# streams_v05.net
KiCad netlist of a schematic drawn in EAGLE
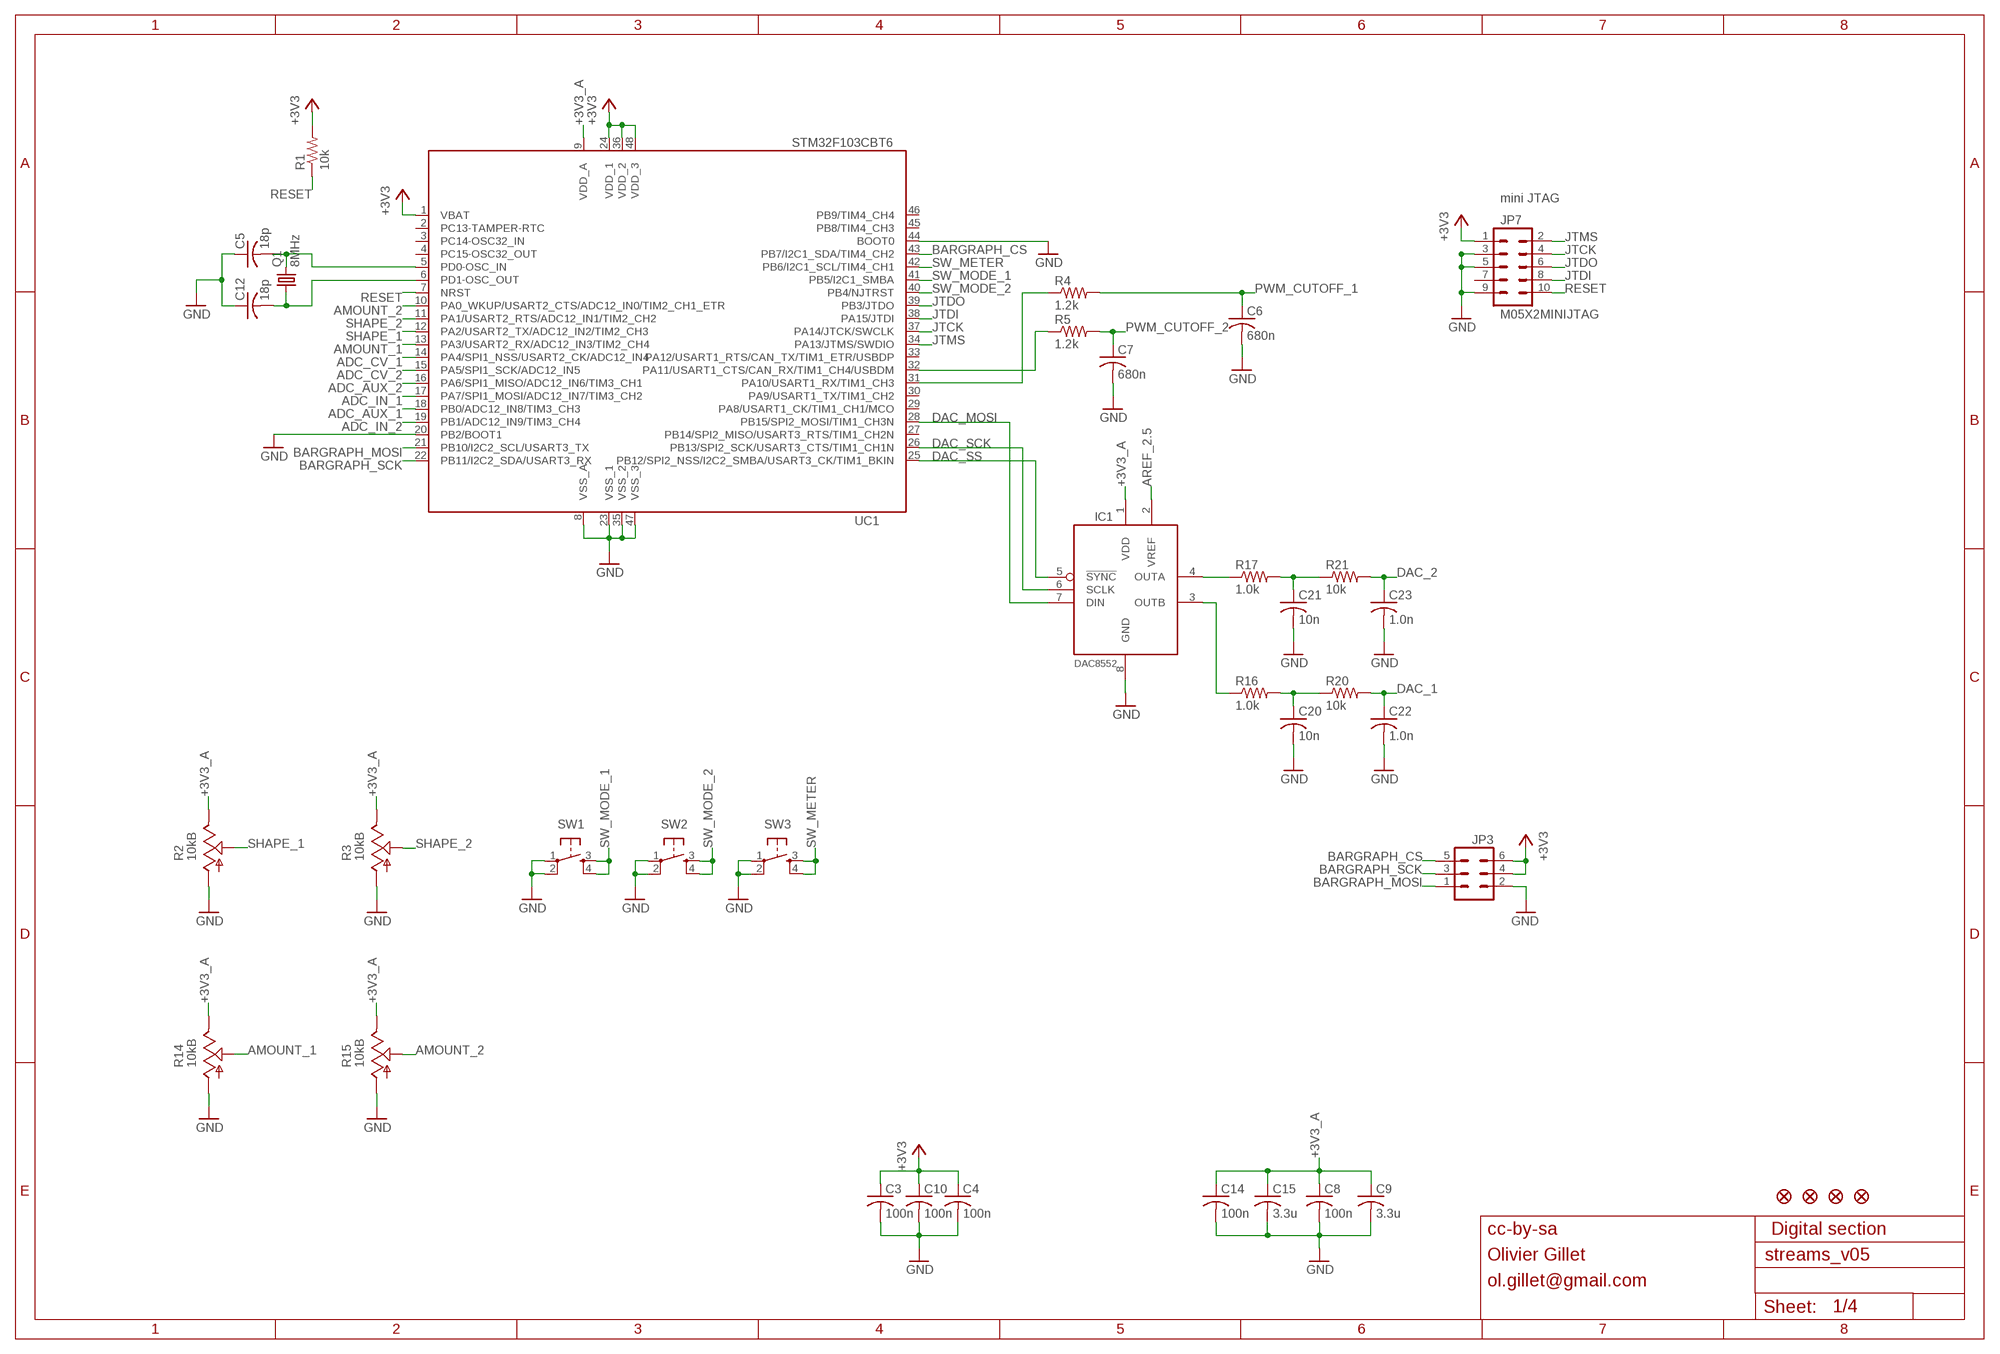
[diagram p0: schematic, sheet 1]
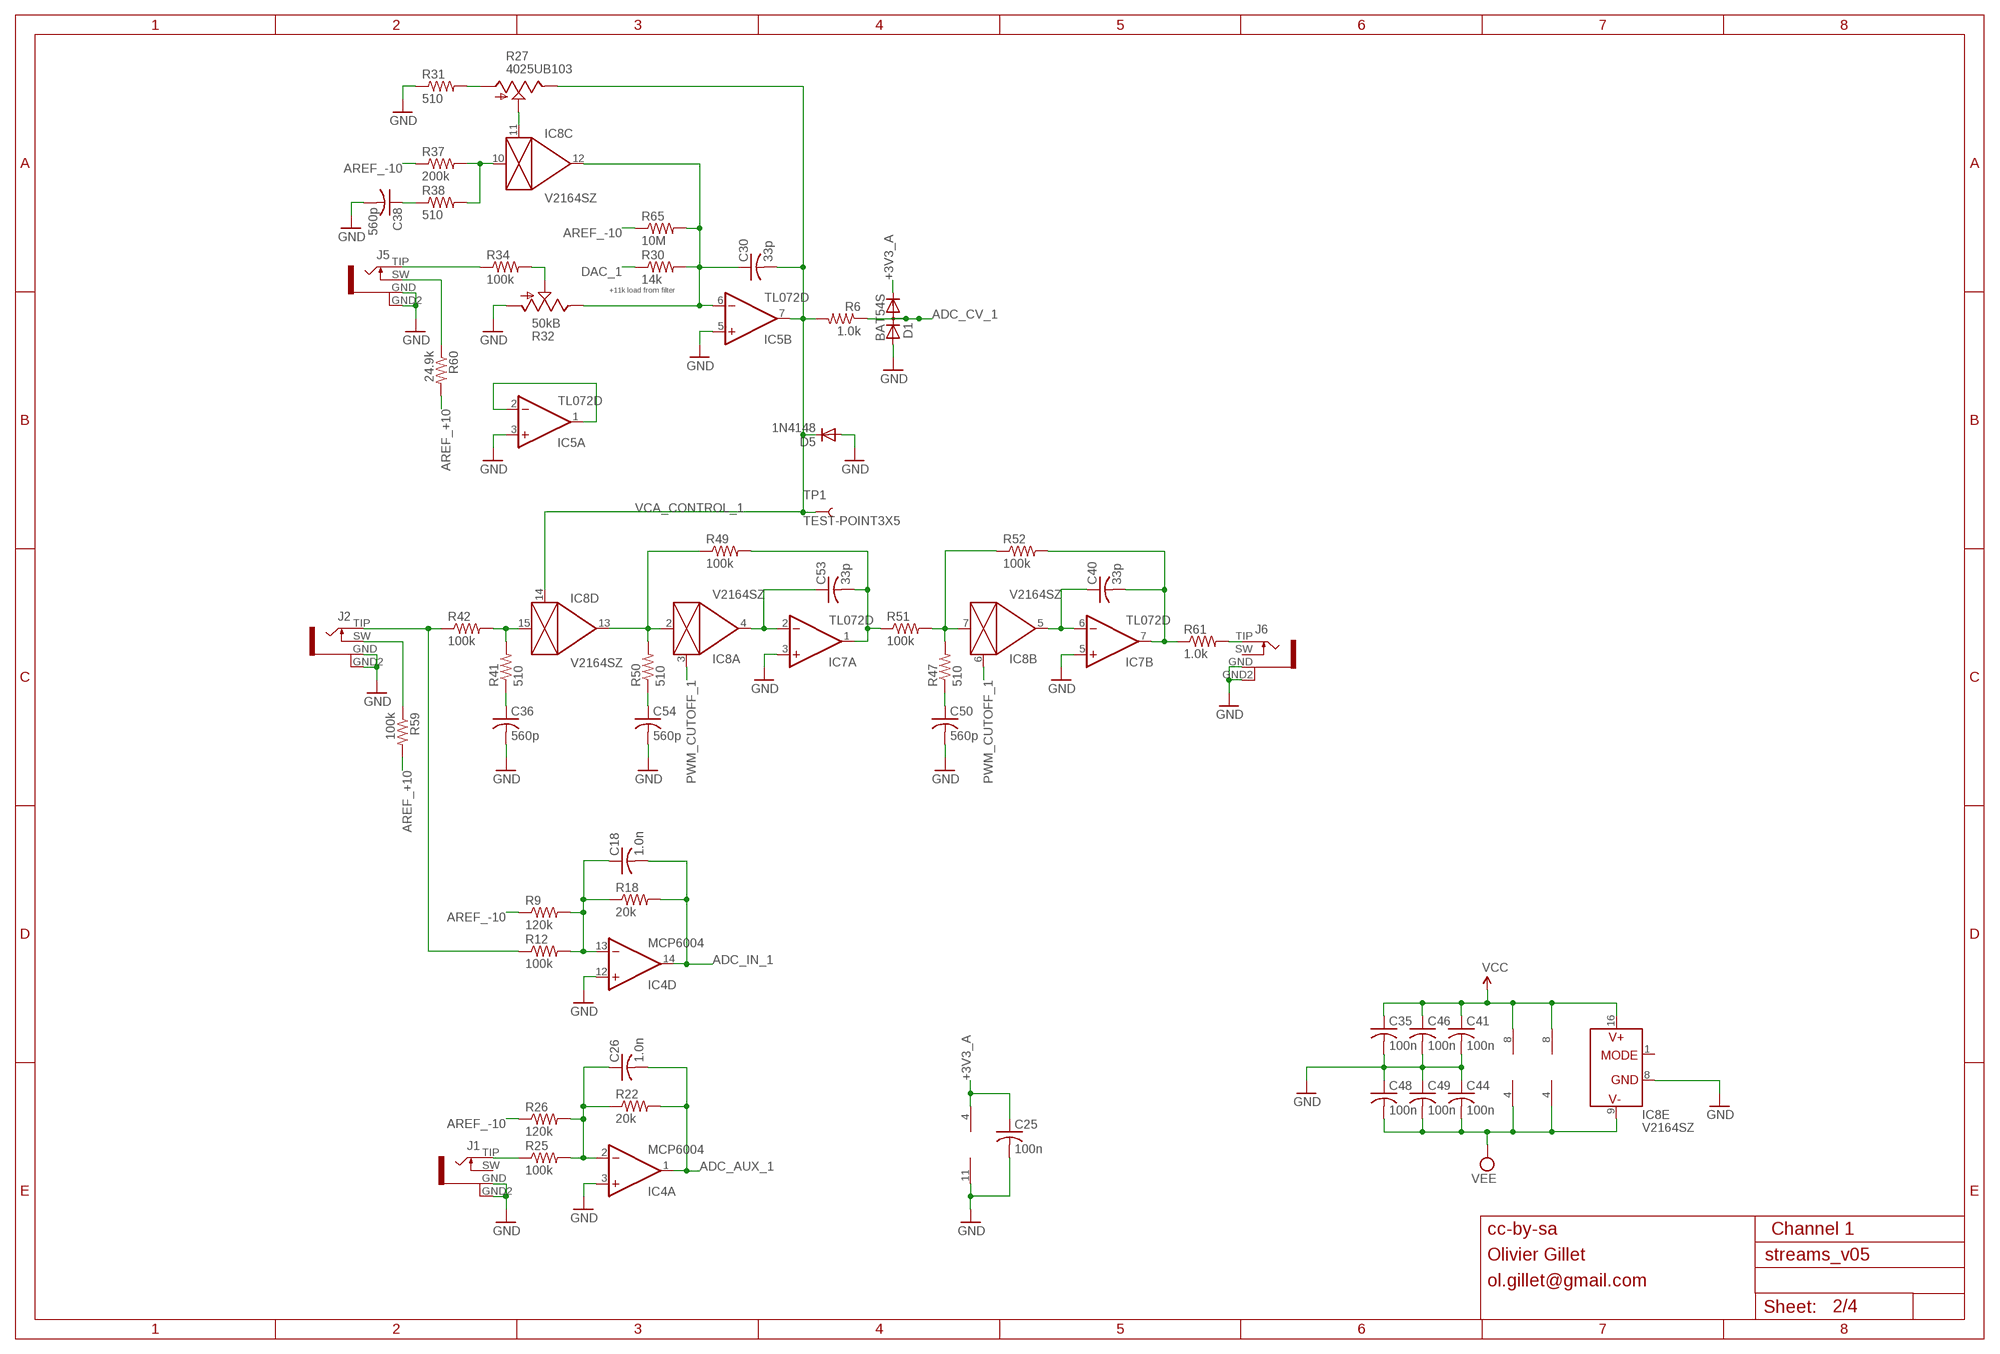
[diagram p1: schematic, sheet 2]
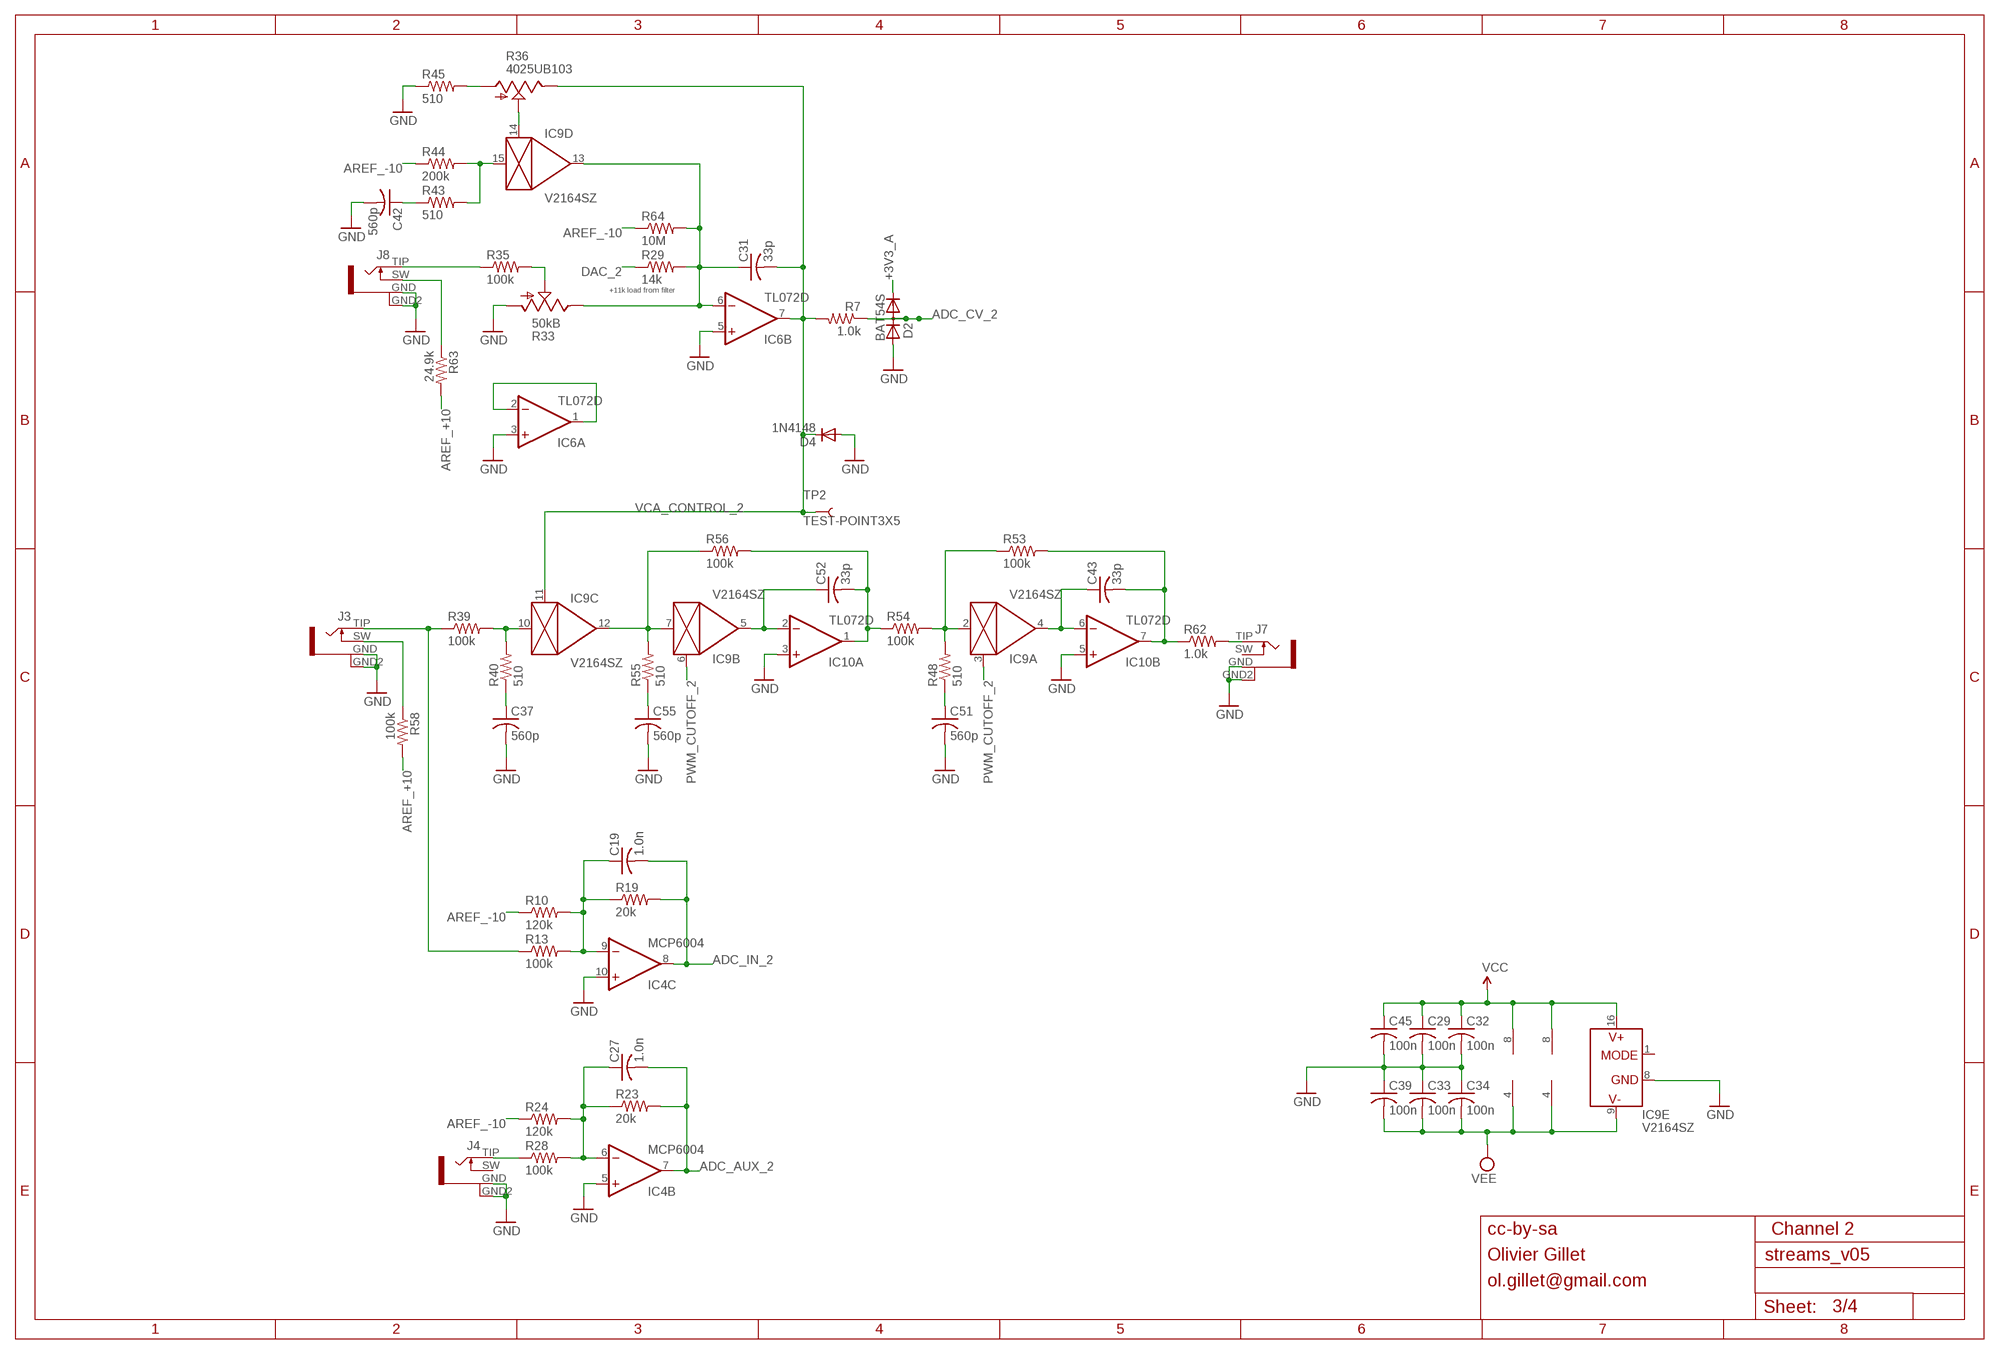
[diagram p2: schematic, sheet 3]
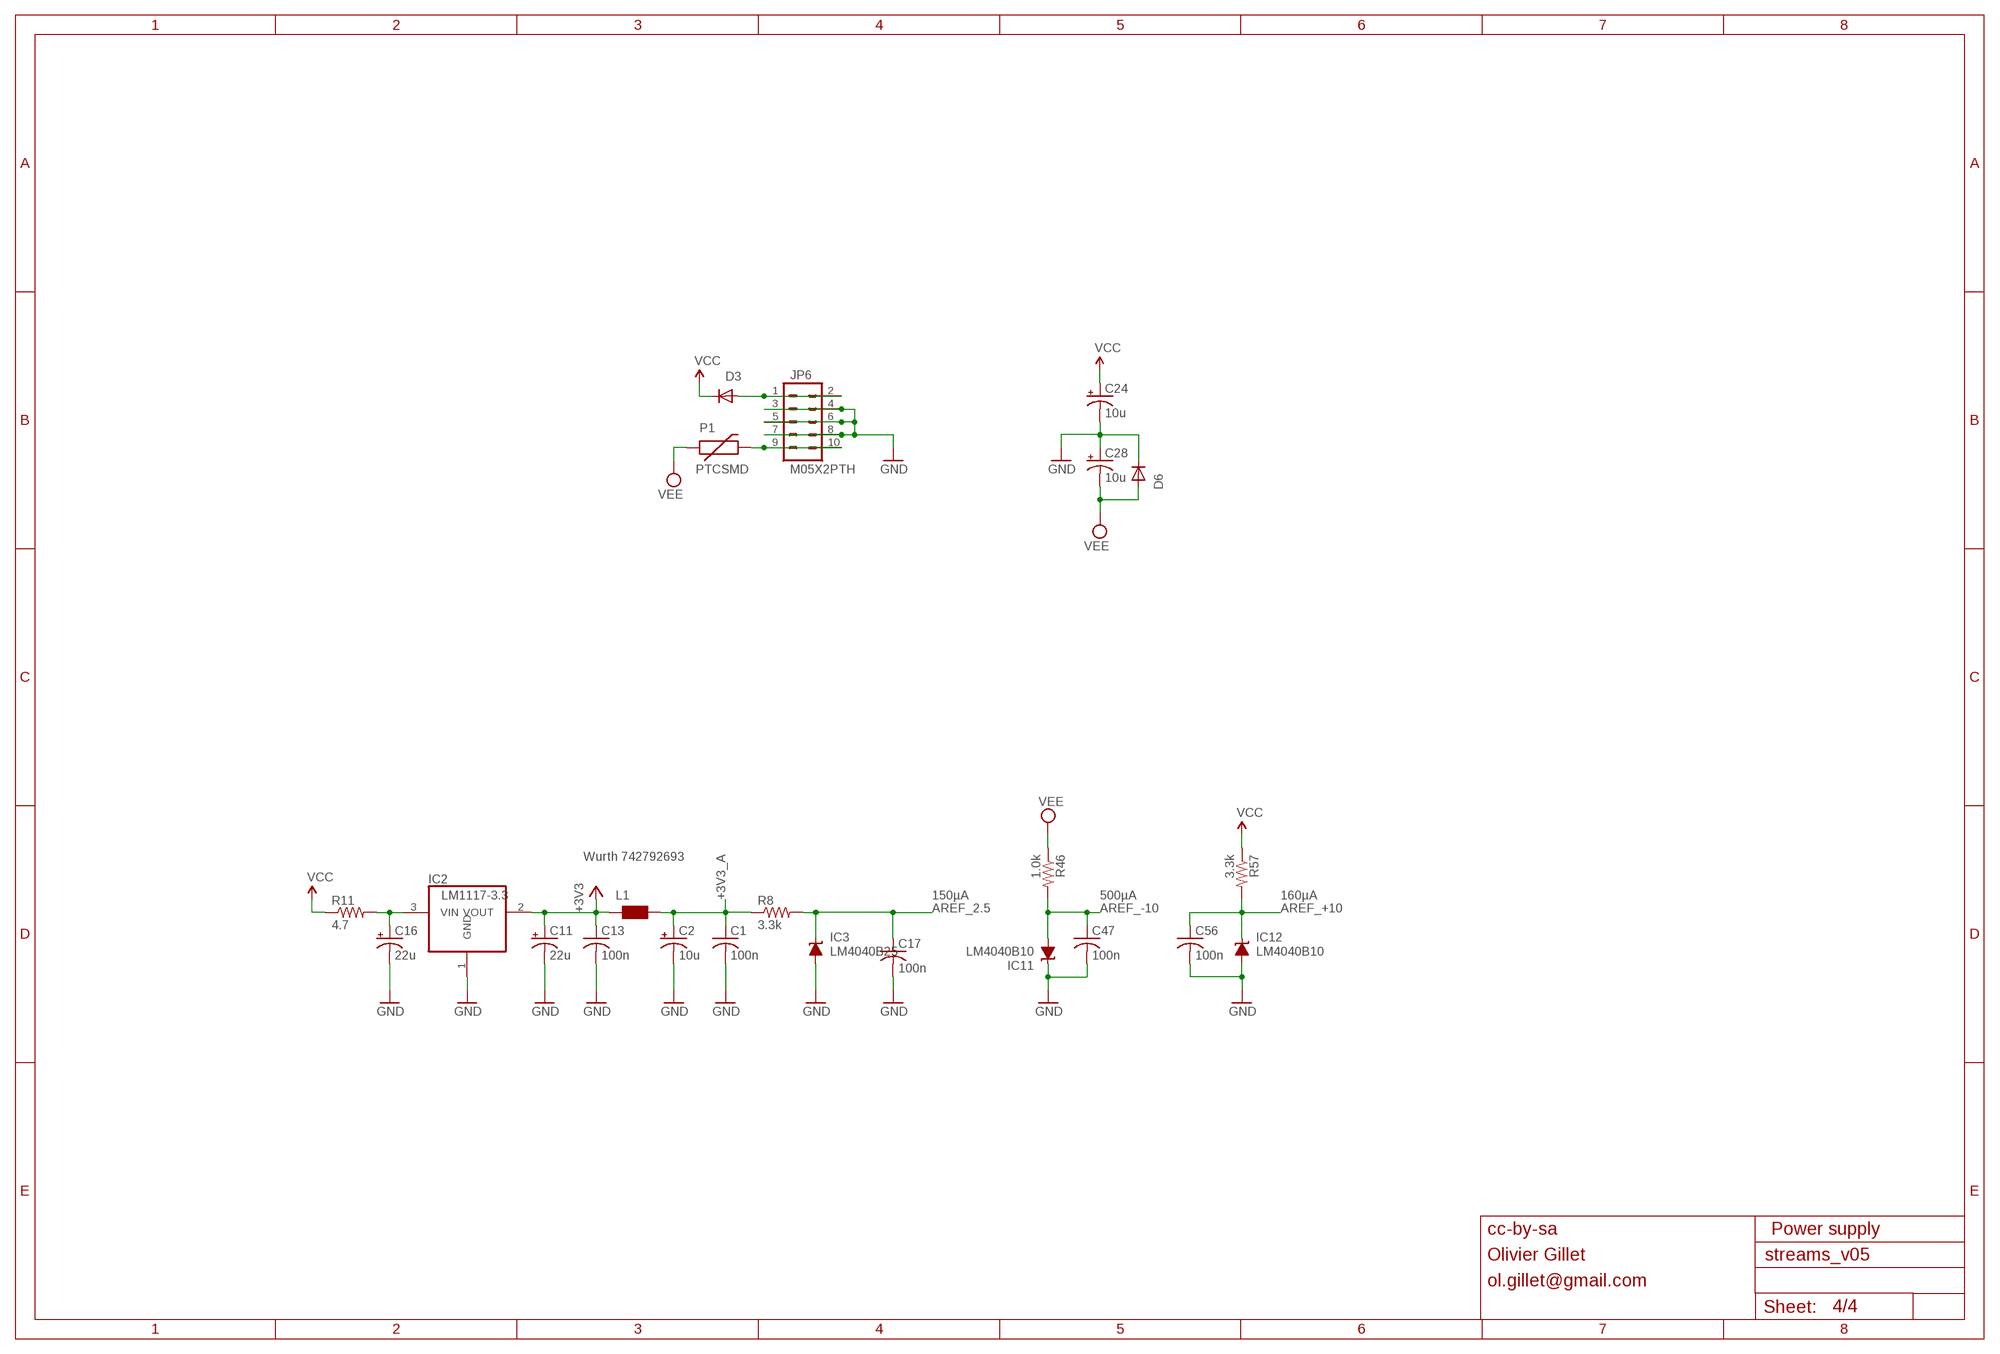
[diagram p3: schematic, sheet 4]

(export (version "E")
  (design (tool "Eeschema 10.0.6"))
  (components
    (comp (ref "C1")
      (value "100n")
      (footprint "eagle-import:C0603")
      (libsource (lib "eagle-import") (part "C-USC0603"))
    )
    (comp (ref "C2")
      (value "10u")
      (footprint "eagle-import:PANASONIC_B")
      (libsource (lib "eagle-import") (part "CPOL-USB"))
    )
    (comp (ref "C11")
      (value "22u")
      (footprint "eagle-import:PANASONIC_B")
      (libsource (lib "eagle-import") (part "CPOL-USB"))
    )
    (comp (ref "C13")
      (value "100n")
      (footprint "eagle-import:C0603")
      (libsource (lib "eagle-import") (part "C-USC0603"))
    )
    (comp (ref "C16")
      (value "22u")
      (footprint "eagle-import:PANASONIC_C")
      (libsource (lib "eagle-import") (part "CPOL-USC"))
    )
    (comp (ref "C17")
      (value "100n")
      (footprint "eagle-import:C0603")
      (libsource (lib "eagle-import") (part "C-USC0603"))
    )
    (comp (ref "C24")
      (value "10u")
      (footprint "eagle-import:PANASONIC_B")
      (libsource (lib "eagle-import") (part "CPOL-USB"))
    )
    (comp (ref "C28")
      (value "10u")
      (footprint "eagle-import:PANASONIC_B")
      (libsource (lib "eagle-import") (part "CPOL-USB"))
    )
    (comp (ref "C47")
      (value "100n")
      (footprint "eagle-import:C0603")
      (libsource (lib "eagle-import") (part "C-USC0603"))
    )
    (comp (ref "C56")
      (value "100n")
      (footprint "eagle-import:C0603")
      (libsource (lib "eagle-import") (part "C-USC0603"))
    )
    (comp (ref "D3")
      (value "1N5819HW")
      (footprint "eagle-import:SOD123")
      (libsource (lib "eagle-import") (part "DIODE-SOD123"))
    )
    (comp (ref "D6")
      (value "1N5819HW")
      (footprint "eagle-import:SOD123")
      (libsource (lib "eagle-import") (part "DIODE-SOD123"))
    )
    (comp (ref "IC2")
      (value "LM1117-3.3")
      (footprint "eagle-import:SOT223")
      (libsource (lib "eagle-import") (part "REG1117"))
    )
    (comp (ref "IC3")
      (value "LM4040B25")
      (footprint "eagle-import:DBZ_R-PDSO-G3")
      (libsource (lib "eagle-import") (part "LM4041DBZB12"))
    )
    (comp (ref "IC11")
      (value "LM4040B10")
      (footprint "eagle-import:DBZ_R-PDSO-G3")
      (libsource (lib "eagle-import") (part "LM4041DBZB12"))
    )
    (comp (ref "IC12")
      (value "LM4040B10")
      (footprint "eagle-import:DBZ_R-PDSO-G3")
      (libsource (lib "eagle-import") (part "LM4041DBZB12"))
    )
    (comp (ref "JP6")
      (value "M05X2PTH")
      (footprint "eagle-import:AVR_ICSP")
      (libsource (lib "eagle-import") (part "M05X2PTH"))
    )
    (comp (ref "L1")
      (value "WE-CBF_0603")
      (footprint "eagle-import:0603")
      (libsource (lib "eagle-import") (part "WE-CBF_0603"))
    )
    (comp (ref "P1")
      (value "PTCSMD")
      (footprint "eagle-import:PTC-1206")
      (libsource (lib "eagle-import") (part "PTCSMD"))
    )
    (comp (ref "R8")
      (value "3.3k")
      (footprint "eagle-import:R0603")
      (libsource (lib "eagle-import") (part "R-US_R0603"))
    )
    (comp (ref "R11")
      (value "4.7")
      (footprint "eagle-import:R1206")
      (libsource (lib "eagle-import") (part "R-US_R1206"))
    )
    (comp (ref "R46")
      (value "1.0k")
      (footprint "eagle-import:R0603")
      (libsource (lib "eagle-import") (part "R-US_R0603"))
    )
    (comp (ref "R57")
      (value "3.3k")
      (footprint "eagle-import:R0603")
      (libsource (lib "eagle-import") (part "R-US_R0603"))
    )
    (comp (ref "C19")
      (value "1.0n")
      (footprint "eagle-import:C0603")
      (libsource (lib "eagle-import") (part "C-USC0603"))
    )
    (comp (ref "C27")
      (value "1.0n")
      (footprint "eagle-import:C0603")
      (libsource (lib "eagle-import") (part "C-USC0603"))
    )
    (comp (ref "C29")
      (value "100n")
      (footprint "eagle-import:C0603")
      (libsource (lib "eagle-import") (part "C-USC0603"))
    )
    (comp (ref "C31")
      (value "33p")
      (footprint "eagle-import:C0603")
      (libsource (lib "eagle-import") (part "C-USC0603"))
    )
    (comp (ref "C32")
      (value "100n")
      (footprint "eagle-import:C0603")
      (libsource (lib "eagle-import") (part "C-USC0603"))
    )
    (comp (ref "C33")
      (value "100n")
      (footprint "eagle-import:C0603")
      (libsource (lib "eagle-import") (part "C-USC0603"))
    )
    (comp (ref "C34")
      (value "100n")
      (footprint "eagle-import:C0603")
      (libsource (lib "eagle-import") (part "C-USC0603"))
    )
    (comp (ref "C37")
      (value "560p")
      (footprint "eagle-import:C0603")
      (libsource (lib "eagle-import") (part "C-USC0603"))
    )
    (comp (ref "C39")
      (value "100n")
      (footprint "eagle-import:C0603")
      (libsource (lib "eagle-import") (part "C-USC0603"))
    )
    (comp (ref "C42")
      (value "560p")
      (footprint "eagle-import:C0603")
      (libsource (lib "eagle-import") (part "C-USC0603"))
    )
    (comp (ref "C43")
      (value "33p")
      (footprint "eagle-import:C0603")
      (libsource (lib "eagle-import") (part "C-USC0603"))
    )
    (comp (ref "C45")
      (value "100n")
      (footprint "eagle-import:C0603")
      (libsource (lib "eagle-import") (part "C-USC0603"))
    )
    (comp (ref "C51")
      (value "560p")
      (footprint "eagle-import:C0603")
      (libsource (lib "eagle-import") (part "C-USC0603"))
    )
    (comp (ref "C52")
      (value "33p")
      (footprint "eagle-import:C0603")
      (libsource (lib "eagle-import") (part "C-USC0603"))
    )
    (comp (ref "C55")
      (value "560p")
      (footprint "eagle-import:C0603")
      (libsource (lib "eagle-import") (part "C-USC0603"))
    )
    (comp (ref "D2")
      (value "BAT54S")
      (footprint "eagle-import:SOT23")
      (libsource (lib "eagle-import") (part "DIODE_2CACA-SOT23"))
    )
    (comp (ref "D4")
      (value "1N4148")
      (footprint "eagle-import:SOD323-W")
      (libsource (lib "eagle-import") (part "DIODE-SOD323-W"))
    )
    (comp (ref "IC4")
      (value "MCP6004")
      (footprint "eagle-import:SO14")
      (libsource (lib "eagle-import") (part "TL074D"))
    )
    (comp (ref "IC6")
      (value "TL072D")
      (footprint "eagle-import:SO08")
      (libsource (lib "eagle-import") (part "TL072D"))
    )
    (comp (ref "IC9")
      (value "V2164SZ")
      (footprint "eagle-import:SOIC16N")
      (libsource (lib "eagle-import") (part "SSM2164S"))
    )
    (comp (ref "IC10")
      (value "TL072D")
      (footprint "eagle-import:SO08")
      (libsource (lib "eagle-import") (part "TL072D"))
    )
    (comp (ref "J3")
      (value "PJ301WQP")
      (footprint "eagle-import:WQP_PJ_301BM_WIDER")
      (libsource (lib "eagle-import") (part "PJ301WQP"))
    )
    (comp (ref "J4")
      (value "PJ301WQP")
      (footprint "eagle-import:WQP_PJ_301BM_WIDER")
      (libsource (lib "eagle-import") (part "PJ301WQP"))
    )
    (comp (ref "J7")
      (value "PJ301WQP")
      (footprint "eagle-import:WQP_PJ_301BM_WIDER")
      (libsource (lib "eagle-import") (part "PJ301WQP"))
    )
    (comp (ref "J8")
      (value "PJ301WQP")
      (footprint "eagle-import:WQP_PJ_301BM_WIDER")
      (libsource (lib "eagle-import") (part "PJ301WQP"))
    )
    (comp (ref "R7")
      (value "1.0k")
      (footprint "eagle-import:R0603")
      (libsource (lib "eagle-import") (part "R-US_R0603"))
    )
    (comp (ref "R10")
      (value "120k")
      (footprint "eagle-import:R0603")
      (libsource (lib "eagle-import") (part "R-US_R0603"))
    )
    (comp (ref "R13")
      (value "100k")
      (footprint "eagle-import:R0603")
      (libsource (lib "eagle-import") (part "R-US_R0603"))
    )
    (comp (ref "R19")
      (value "20k")
      (footprint "eagle-import:R0603")
      (libsource (lib "eagle-import") (part "R-US_R0603"))
    )
    (comp (ref "R23")
      (value "20k")
      (footprint "eagle-import:R0603")
      (libsource (lib "eagle-import") (part "R-US_R0603"))
    )
    (comp (ref "R24")
      (value "120k")
      (footprint "eagle-import:R0603")
      (libsource (lib "eagle-import") (part "R-US_R0603"))
    )
    (comp (ref "R28")
      (value "100k")
      (footprint "eagle-import:R0603")
      (libsource (lib "eagle-import") (part "R-US_R0603"))
    )
    (comp (ref "R29")
      (value "14k")
      (footprint "eagle-import:R0603")
      (libsource (lib "eagle-import") (part "R-US_R0603"))
    )
    (comp (ref "R33")
      (value "50kB")
      (footprint "eagle-import:ALPS_POT_VERTICAL_PS")
      (libsource (lib "eagle-import") (part "POT_USVERTICAL_PS"))
    )
    (comp (ref "R35")
      (value "100k")
      (footprint "eagle-import:R0603")
      (libsource (lib "eagle-import") (part "R-US_R0603"))
    )
    (comp (ref "R36")
      (value "4025UB103")
      (footprint "eagle-import:ALPS_POT_VERTICAL")
      (libsource (lib "eagle-import") (part "POT_USVERTICAL"))
    )
    (comp (ref "R39")
      (value "100k")
      (footprint "eagle-import:R0603")
      (libsource (lib "eagle-import") (part "R-US_R0603"))
    )
    (comp (ref "R40")
      (value "510")
      (footprint "eagle-import:R0603")
      (libsource (lib "eagle-import") (part "R-US_R0603"))
    )
    (comp (ref "R43")
      (value "510")
      (footprint "eagle-import:R0603")
      (libsource (lib "eagle-import") (part "R-US_R0603"))
    )
    (comp (ref "R44")
      (value "200k")
      (footprint "eagle-import:R0603")
      (libsource (lib "eagle-import") (part "R-US_R0603"))
    )
    (comp (ref "R45")
      (value "510")
      (footprint "eagle-import:R0603")
      (libsource (lib "eagle-import") (part "R-US_R0603"))
    )
    (comp (ref "R48")
      (value "510")
      (footprint "eagle-import:R0603")
      (libsource (lib "eagle-import") (part "R-US_R0603"))
    )
    (comp (ref "R53")
      (value "100k")
      (footprint "eagle-import:R0603")
      (libsource (lib "eagle-import") (part "R-US_R0603"))
    )
    (comp (ref "R54")
      (value "100k")
      (footprint "eagle-import:R0603")
      (libsource (lib "eagle-import") (part "R-US_R0603"))
    )
    (comp (ref "R55")
      (value "510")
      (footprint "eagle-import:R0603")
      (libsource (lib "eagle-import") (part "R-US_R0603"))
    )
    (comp (ref "R56")
      (value "100k")
      (footprint "eagle-import:R0603")
      (libsource (lib "eagle-import") (part "R-US_R0603"))
    )
    (comp (ref "R58")
      (value "100k")
      (footprint "eagle-import:R0603")
      (libsource (lib "eagle-import") (part "R-US_R0603"))
    )
    (comp (ref "R62")
      (value "1.0k")
      (footprint "eagle-import:R0603")
      (libsource (lib "eagle-import") (part "R-US_R0603"))
    )
    (comp (ref "R63")
      (value "24.9k")
      (footprint "eagle-import:R0603")
      (libsource (lib "eagle-import") (part "R-US_R0603"))
    )
    (comp (ref "R64")
      (value "10M")
      (footprint "eagle-import:R0603")
      (libsource (lib "eagle-import") (part "R-US_R0603"))
    )
    (comp (ref "TP2")
      (value "TEST-POINT3X5")
      (footprint "eagle-import:PAD.03X.05")
      (libsource (lib "eagle-import") (part "TEST-POINT3X5"))
    )
    (comp (ref "C18")
      (value "1.0n")
      (footprint "eagle-import:C0603")
      (libsource (lib "eagle-import") (part "C-USC0603"))
    )
    (comp (ref "C25")
      (value "100n")
      (footprint "eagle-import:C0603")
      (libsource (lib "eagle-import") (part "C-USC0603"))
    )
    (comp (ref "C26")
      (value "1.0n")
      (footprint "eagle-import:C0603")
      (libsource (lib "eagle-import") (part "C-USC0603"))
    )
    (comp (ref "C30")
      (value "33p")
      (footprint "eagle-import:C0603")
      (libsource (lib "eagle-import") (part "C-USC0603"))
    )
    (comp (ref "C35")
      (value "100n")
      (footprint "eagle-import:C0603")
      (libsource (lib "eagle-import") (part "C-USC0603"))
    )
    (comp (ref "C36")
      (value "560p")
      (footprint "eagle-import:C0603")
      (libsource (lib "eagle-import") (part "C-USC0603"))
    )
    (comp (ref "C38")
      (value "560p")
      (footprint "eagle-import:C0603")
      (libsource (lib "eagle-import") (part "C-USC0603"))
    )
    (comp (ref "C40")
      (value "33p")
      (footprint "eagle-import:C0603")
      (libsource (lib "eagle-import") (part "C-USC0603"))
    )
    (comp (ref "C41")
      (value "100n")
      (footprint "eagle-import:C0603")
      (libsource (lib "eagle-import") (part "C-USC0603"))
    )
    (comp (ref "C44")
      (value "100n")
      (footprint "eagle-import:C0603")
      (libsource (lib "eagle-import") (part "C-USC0603"))
    )
    (comp (ref "C46")
      (value "100n")
      (footprint "eagle-import:C0603")
      (libsource (lib "eagle-import") (part "C-USC0603"))
    )
    (comp (ref "C48")
      (value "100n")
      (footprint "eagle-import:C0603")
      (libsource (lib "eagle-import") (part "C-USC0603"))
    )
    (comp (ref "C49")
      (value "100n")
      (footprint "eagle-import:C0603")
      (libsource (lib "eagle-import") (part "C-USC0603"))
    )
    (comp (ref "C50")
      (value "560p")
      (footprint "eagle-import:C0603")
      (libsource (lib "eagle-import") (part "C-USC0603"))
    )
    (comp (ref "C53")
      (value "33p")
      (footprint "eagle-import:C0603")
      (libsource (lib "eagle-import") (part "C-USC0603"))
    )
    (comp (ref "C54")
      (value "560p")
      (footprint "eagle-import:C0603")
      (libsource (lib "eagle-import") (part "C-USC0603"))
    )
    (comp (ref "D1")
      (value "BAT54S")
      (footprint "eagle-import:SOT23")
      (libsource (lib "eagle-import") (part "DIODE_2CACA-SOT23"))
    )
    (comp (ref "D5")
      (value "1N4148")
      (footprint "eagle-import:SOD323-W")
      (libsource (lib "eagle-import") (part "DIODE-SOD323-W"))
    )
    (comp (ref "IC5")
      (value "TL072D")
      (footprint "eagle-import:SO08")
      (libsource (lib "eagle-import") (part "TL072D"))
    )
    (comp (ref "IC7")
      (value "TL072D")
      (footprint "eagle-import:SO08")
      (libsource (lib "eagle-import") (part "TL072D"))
    )
    (comp (ref "IC8")
      (value "V2164SZ")
      (footprint "eagle-import:SOIC16N")
      (libsource (lib "eagle-import") (part "SSM2164S"))
    )
    (comp (ref "J1")
      (value "PJ301WQP")
      (footprint "eagle-import:WQP_PJ_301BM_WIDER")
      (libsource (lib "eagle-import") (part "PJ301WQP"))
    )
    (comp (ref "J2")
      (value "PJ301WQP")
      (footprint "eagle-import:WQP_PJ_301BM_WIDER")
      (libsource (lib "eagle-import") (part "PJ301WQP"))
    )
    (comp (ref "J5")
      (value "PJ301WQP")
      (footprint "eagle-import:WQP_PJ_301BM_WIDER")
      (libsource (lib "eagle-import") (part "PJ301WQP"))
    )
    (comp (ref "J6")
      (value "PJ301WQP")
      (footprint "eagle-import:WQP_PJ_301BM_WIDER")
      (libsource (lib "eagle-import") (part "PJ301WQP"))
    )
    (comp (ref "R6")
      (value "1.0k")
      (footprint "eagle-import:R0603")
      (libsource (lib "eagle-import") (part "R-US_R0603"))
    )
    (comp (ref "R9")
      (value "120k")
      (footprint "eagle-import:R0603")
      (libsource (lib "eagle-import") (part "R-US_R0603"))
    )
    (comp (ref "R12")
      (value "100k")
      (footprint "eagle-import:R0603")
      (libsource (lib "eagle-import") (part "R-US_R0603"))
    )
    (comp (ref "R18")
      (value "20k")
      (footprint "eagle-import:R0603")
      (libsource (lib "eagle-import") (part "R-US_R0603"))
    )
    (comp (ref "R22")
      (value "20k")
      (footprint "eagle-import:R0603")
      (libsource (lib "eagle-import") (part "R-US_R0603"))
    )
    (comp (ref "R25")
      (value "100k")
      (footprint "eagle-import:R0603")
      (libsource (lib "eagle-import") (part "R-US_R0603"))
    )
    (comp (ref "R26")
      (value "120k")
      (footprint "eagle-import:R0603")
      (libsource (lib "eagle-import") (part "R-US_R0603"))
    )
    (comp (ref "R27")
      (value "4025UB103")
      (footprint "eagle-import:ALPS_POT_VERTICAL")
      (libsource (lib "eagle-import") (part "POT_USVERTICAL"))
    )
    (comp (ref "R30")
      (value "14k")
      (footprint "eagle-import:R0603")
      (libsource (lib "eagle-import") (part "R-US_R0603"))
    )
    (comp (ref "R31")
      (value "510")
      (footprint "eagle-import:R0603")
      (libsource (lib "eagle-import") (part "R-US_R0603"))
    )
    (comp (ref "R32")
      (value "50kB")
      (footprint "eagle-import:ALPS_POT_VERTICAL_PS")
      (libsource (lib "eagle-import") (part "POT_USVERTICAL_PS"))
    )
    (comp (ref "R34")
      (value "100k")
      (footprint "eagle-import:R0603")
      (libsource (lib "eagle-import") (part "R-US_R0603"))
    )
    (comp (ref "R37")
      (value "200k")
      (footprint "eagle-import:R0603")
      (libsource (lib "eagle-import") (part "R-US_R0603"))
    )
    (comp (ref "R38")
      (value "510")
      (footprint "eagle-import:R0603")
      (libsource (lib "eagle-import") (part "R-US_R0603"))
    )
    (comp (ref "R41")
      (value "510")
      (footprint "eagle-import:R0603")
      (libsource (lib "eagle-import") (part "R-US_R0603"))
    )
    (comp (ref "R42")
      (value "100k")
      (footprint "eagle-import:R0603")
      (libsource (lib "eagle-import") (part "R-US_R0603"))
    )
    (comp (ref "R47")
      (value "510")
      (footprint "eagle-import:R0603")
      (libsource (lib "eagle-import") (part "R-US_R0603"))
    )
    (comp (ref "R49")
      (value "100k")
      (footprint "eagle-import:R0603")
      (libsource (lib "eagle-import") (part "R-US_R0603"))
    )
    (comp (ref "R50")
      (value "510")
      (footprint "eagle-import:R0603")
      (libsource (lib "eagle-import") (part "R-US_R0603"))
    )
    (comp (ref "R51")
      (value "100k")
      (footprint "eagle-import:R0603")
      (libsource (lib "eagle-import") (part "R-US_R0603"))
    )
    (comp (ref "R52")
      (value "100k")
      (footprint "eagle-import:R0603")
      (libsource (lib "eagle-import") (part "R-US_R0603"))
    )
    (comp (ref "R59")
      (value "100k")
      (footprint "eagle-import:R0603")
      (libsource (lib "eagle-import") (part "R-US_R0603"))
    )
    (comp (ref "R60")
      (value "24.9k")
      (footprint "eagle-import:R0603")
      (libsource (lib "eagle-import") (part "R-US_R0603"))
    )
    (comp (ref "R61")
      (value "1.0k")
      (footprint "eagle-import:R0603")
      (libsource (lib "eagle-import") (part "R-US_R0603"))
    )
    (comp (ref "R65")
      (value "10M")
      (footprint "eagle-import:R0603")
      (libsource (lib "eagle-import") (part "R-US_R0603"))
    )
    (comp (ref "TP1")
      (value "TEST-POINT3X5")
      (footprint "eagle-import:PAD.03X.05")
      (libsource (lib "eagle-import") (part "TEST-POINT3X5"))
    )
    (comp (ref "C3")
      (value "100n")
      (footprint "eagle-import:C0603")
      (libsource (lib "eagle-import") (part "C-USC0603"))
    )
    (comp (ref "C4")
      (value "100n")
      (footprint "eagle-import:C0603")
      (libsource (lib "eagle-import") (part "C-USC0603"))
    )
    (comp (ref "C5")
      (value "18p")
      (footprint "eagle-import:C0603")
      (libsource (lib "eagle-import") (part "C-USC0603"))
    )
    (comp (ref "C6")
      (value "680n")
      (footprint "eagle-import:C0603")
      (libsource (lib "eagle-import") (part "C-USC0603"))
    )
    (comp (ref "C7")
      (value "680n")
      (footprint "eagle-import:C0603")
      (libsource (lib "eagle-import") (part "C-USC0603"))
    )
    (comp (ref "C8")
      (value "100n")
      (footprint "eagle-import:C0603")
      (libsource (lib "eagle-import") (part "C-USC0603"))
    )
    (comp (ref "C9")
      (value "3.3u")
      (footprint "eagle-import:C0603")
      (libsource (lib "eagle-import") (part "C-USC0603"))
    )
    (comp (ref "C10")
      (value "100n")
      (footprint "eagle-import:C0603")
      (libsource (lib "eagle-import") (part "C-USC0603"))
    )
    (comp (ref "C12")
      (value "18p")
      (footprint "eagle-import:C0603")
      (libsource (lib "eagle-import") (part "C-USC0603"))
    )
    (comp (ref "C14")
      (value "100n")
      (footprint "eagle-import:C0603")
      (libsource (lib "eagle-import") (part "C-USC0603"))
    )
    (comp (ref "C15")
      (value "3.3u")
      (footprint "eagle-import:C0603")
      (libsource (lib "eagle-import") (part "C-USC0603"))
    )
    (comp (ref "C20")
      (value "10n")
      (footprint "eagle-import:C0603")
      (libsource (lib "eagle-import") (part "C-USC0603"))
    )
    (comp (ref "C21")
      (value "10n")
      (footprint "eagle-import:C0603")
      (libsource (lib "eagle-import") (part "C-USC0603"))
    )
    (comp (ref "C22")
      (value "1.0n")
      (footprint "eagle-import:C0603")
      (libsource (lib "eagle-import") (part "C-USC0603"))
    )
    (comp (ref "C23")
      (value "1.0n")
      (footprint "eagle-import:C0603")
      (libsource (lib "eagle-import") (part "C-USC0603"))
    )
    (comp (ref "IC1")
      (value "DAC8552")
      (footprint "eagle-import:MSOP-8")
      (libsource (lib "eagle-import") (part "DAC8552"))
    )
    (comp (ref "JP1")
      (value "FIDUCIAL1X2")
      (footprint "eagle-import:FIDUCIAL-1X2")
      (libsource (lib "eagle-import") (part "FIDUCIAL1X2"))
    )
    (comp (ref "JP2")
      (value "FIDUCIAL1X2")
      (footprint "eagle-import:FIDUCIAL-1X2")
      (libsource (lib "eagle-import") (part "FIDUCIAL1X2"))
    )
    (comp (ref "JP3")
      (value "M03X2BOTTOM")
      (footprint "eagle-import:2X3_BOTTOM")
      (libsource (lib "eagle-import") (part "M03X2BOTTOM"))
    )
    (comp (ref "JP4")
      (value "FIDUCIAL1X2")
      (footprint "eagle-import:FIDUCIAL-1X2")
      (libsource (lib "eagle-import") (part "FIDUCIAL1X2"))
    )
    (comp (ref "JP5")
      (value "FIDUCIAL1X2")
      (footprint "eagle-import:FIDUCIAL-1X2")
      (libsource (lib "eagle-import") (part "FIDUCIAL1X2"))
    )
    (comp (ref "JP7")
      (value "M05X2MINIJTAG")
      (footprint "eagle-import:2X5-1.27")
      (libsource (lib "eagle-import") (part "M05X2MINIJTAG"))
    )
    (comp (ref "Q1")
      (value "8MHz")
      (footprint "eagle-import:HC49UP")
      (libsource (lib "eagle-import") (part "CRYSTALHC49UP"))
    )
    (comp (ref "R1")
      (value "10k")
      (footprint "eagle-import:R0603")
      (libsource (lib "eagle-import") (part "R-US_R0603"))
    )
    (comp (ref "R2")
      (value "10kB")
      (footprint "eagle-import:ALPS_POT_VERTICAL_PS")
      (libsource (lib "eagle-import") (part "POT_USVERTICAL_PS"))
    )
    (comp (ref "R3")
      (value "10kB")
      (footprint "eagle-import:ALPS_POT_VERTICAL_PS")
      (libsource (lib "eagle-import") (part "POT_USVERTICAL_PS"))
    )
    (comp (ref "R4")
      (value "1.2k")
      (footprint "eagle-import:R0603")
      (libsource (lib "eagle-import") (part "R-US_R0603"))
    )
    (comp (ref "R5")
      (value "1.2k")
      (footprint "eagle-import:R0603")
      (libsource (lib "eagle-import") (part "R-US_R0603"))
    )
    (comp (ref "R14")
      (value "10kB")
      (footprint "eagle-import:ALPS_POT_VERTICAL_PS")
      (libsource (lib "eagle-import") (part "POT_USVERTICAL_PS"))
    )
    (comp (ref "R15")
      (value "10kB")
      (footprint "eagle-import:ALPS_POT_VERTICAL_PS")
      (libsource (lib "eagle-import") (part "POT_USVERTICAL_PS"))
    )
    (comp (ref "R16")
      (value "1.0k")
      (footprint "eagle-import:R0603")
      (libsource (lib "eagle-import") (part "R-US_R0603"))
    )
    (comp (ref "R17")
      (value "1.0k")
      (footprint "eagle-import:R0603")
      (libsource (lib "eagle-import") (part "R-US_R0603"))
    )
    (comp (ref "R20")
      (value "10k")
      (footprint "eagle-import:R0603")
      (libsource (lib "eagle-import") (part "R-US_R0603"))
    )
    (comp (ref "R21")
      (value "10k")
      (footprint "eagle-import:R0603")
      (libsource (lib "eagle-import") (part "R-US_R0603"))
    )
    (comp (ref "SW1")
      (value "TAC_SWITCHPTH")
      (footprint "eagle-import:TACTILE-PTH")
      (libsource (lib "eagle-import") (part "TAC_SWITCHPTH"))
    )
    (comp (ref "SW2")
      (value "TAC_SWITCHPTH")
      (footprint "eagle-import:TACTILE-PTH")
      (libsource (lib "eagle-import") (part "TAC_SWITCHPTH"))
    )
    (comp (ref "SW3")
      (value "TAC_SWITCHPTH")
      (footprint "eagle-import:TACTILE-PTH")
      (libsource (lib "eagle-import") (part "TAC_SWITCHPTH"))
    )
    (comp (ref "UC1")
      (value "STM32F103CBT6")
      (footprint "eagle-import:LQFP48")
      (libsource (lib "eagle-import") (part "STM32F103CB"))
    )
  )
  (nets
    (net (code "1") (name "+3V3") (class "Default")
      (node (ref "C10") (pin "1") (pinfunction "1_1") (pintype "passive"))
      (node (ref "C11") (pin "+") (pinfunction "+_+") (pintype "passive"))
      (node (ref "C13") (pin "1") (pinfunction "1_1") (pintype "passive"))
      (node (ref "C3") (pin "1") (pinfunction "1_1") (pintype "passive"))
      (node (ref "C4") (pin "1") (pinfunction "1_1") (pintype "passive"))
      (node (ref "IC2") (pin "2") (pinfunction "VOUT_2") (pintype "output"))
      (node (ref "JP3") (pin "4") (pinfunction "4_4") (pintype "passive"))
      (node (ref "JP3") (pin "6") (pinfunction "6_6") (pintype "passive"))
      (node (ref "JP7") (pin "1") (pinfunction "1_1") (pintype "passive"))
      (node (ref "L1") (pin "1") (pinfunction "1_1") (pintype "passive"))
      (node (ref "R1") (pin "2") (pinfunction "2_2") (pintype "passive"))
      (node (ref "UC1") (pin "1") (pinfunction "VBAT_1") (pintype "power_in"))
      (node (ref "UC1") (pin "24") (pinfunction "VDD_1_24") (pintype "power_in"))
      (node (ref "UC1") (pin "36") (pinfunction "VDD_2_36") (pintype "power_in"))
      (node (ref "UC1") (pin "48") (pinfunction "VDD_3_48") (pintype "power_in"))
    )
    (net (code "2") (name "+3V3_A") (class "Default")
      (node (ref "C1") (pin "1") (pinfunction "1_1") (pintype "passive"))
      (node (ref "C14") (pin "1") (pinfunction "1_1") (pintype "passive"))
      (node (ref "C15") (pin "1") (pinfunction "1_1") (pintype "passive"))
      (node (ref "C2") (pin "+") (pinfunction "+_+") (pintype "passive"))
      (node (ref "C25") (pin "1") (pinfunction "1_1") (pintype "passive"))
      (node (ref "C8") (pin "1") (pinfunction "1_1") (pintype "passive"))
      (node (ref "C9") (pin "1") (pinfunction "1_1") (pintype "passive"))
      (node (ref "D1") (pin "2") (pinfunction "C_2") (pintype "passive"))
      (node (ref "D2") (pin "2") (pinfunction "C_2") (pintype "passive"))
      (node (ref "IC1") (pin "1") (pinfunction "VDD_1") (pintype "power_in"))
      (node (ref "IC4") (pin "4") (pinfunction "V+_4") (pintype "power_in"))
      (node (ref "L1") (pin "2") (pinfunction "2_2") (pintype "passive"))
      (node (ref "R14") (pin "P$1") (pinfunction "E_P$1") (pintype "passive"))
      (node (ref "R15") (pin "P$1") (pinfunction "E_P$1") (pintype "passive"))
      (node (ref "R2") (pin "P$1") (pinfunction "E_P$1") (pintype "passive"))
      (node (ref "R3") (pin "P$1") (pinfunction "E_P$1") (pintype "passive"))
      (node (ref "R8") (pin "1") (pinfunction "1_1") (pintype "passive"))
      (node (ref "UC1") (pin "9") (pinfunction "VDD_A_9") (pintype "power_in"))
    )
    (net (code "3") (name "ADC_AUX_1") (class "Default")
      (node (ref "C26") (pin "2") (pinfunction "2_2") (pintype "passive"))
      (node (ref "IC4") (pin "1") (pinfunction "OUT_1") (pintype "output"))
      (node (ref "R22") (pin "2") (pinfunction "2_2") (pintype "passive"))
      (node (ref "UC1") (pin "18") (pinfunction "PB0/ADC12_IN8/TIM3_CH3_18") (pintype "bidirectional"))
    )
    (net (code "4") (name "ADC_AUX_2") (class "Default")
      (node (ref "C27") (pin "2") (pinfunction "2_2") (pintype "passive"))
      (node (ref "IC4") (pin "7") (pinfunction "OUT_7") (pintype "output"))
      (node (ref "R23") (pin "2") (pinfunction "2_2") (pintype "passive"))
      (node (ref "UC1") (pin "16") (pinfunction "PA6/SPI1_MISO/ADC12_IN6/TIM3_CH1_16") (pintype "bidirectional"))
    )
    (net (code "5") (name "ADC_CV_1") (class "Default")
      (node (ref "D1") (pin "3") (pinfunction "AC_3") (pintype "passive"))
      (node (ref "R6") (pin "1") (pinfunction "1_1") (pintype "passive"))
      (node (ref "UC1") (pin "14") (pinfunction "PA4/SPI1_NSS/USART2_CK/ADC12_IN4_14") (pintype "bidirectional"))
    )
    (net (code "6") (name "ADC_CV_2") (class "Default")
      (node (ref "D2") (pin "3") (pinfunction "AC_3") (pintype "passive"))
      (node (ref "R7") (pin "1") (pinfunction "1_1") (pintype "passive"))
      (node (ref "UC1") (pin "15") (pinfunction "PA5/SPI1_SCK/ADC12_IN5_15") (pintype "bidirectional"))
    )
    (net (code "7") (name "ADC_IN_1") (class "Default")
      (node (ref "C18") (pin "2") (pinfunction "2_2") (pintype "passive"))
      (node (ref "IC4") (pin "14") (pinfunction "OUT_14") (pintype "output"))
      (node (ref "R18") (pin "2") (pinfunction "2_2") (pintype "passive"))
      (node (ref "UC1") (pin "17") (pinfunction "PA7/SPI1_MOSI/ADC12_IN7/TIM3_CH2_17") (pintype "bidirectional"))
    )
    (net (code "8") (name "ADC_IN_2") (class "Default")
      (node (ref "C19") (pin "2") (pinfunction "2_2") (pintype "passive"))
      (node (ref "IC4") (pin "8") (pinfunction "OUT_8") (pintype "output"))
      (node (ref "R19") (pin "2") (pinfunction "2_2") (pintype "passive"))
      (node (ref "UC1") (pin "19") (pinfunction "PB1/ADC12_IN9/TIM3_CH4_19") (pintype "bidirectional"))
    )
    (net (code "9") (name "AMOUNT_1") (class "Default")
      (node (ref "R14") (pin "P$2") (pinfunction "S_P$2") (pintype "passive"))
      (node (ref "UC1") (pin "13") (pinfunction "PA3/USART2_RX/ADC12_IN3/TIM2_CH4_13") (pintype "bidirectional"))
    )
    (net (code "10") (name "AMOUNT_2") (class "Default")
      (node (ref "R15") (pin "P$2") (pinfunction "S_P$2") (pintype "passive"))
      (node (ref "UC1") (pin "10") (pinfunction "PA0_WKUP/USART2_CTS/ADC12_IN0/TIM2_CH1_ETR_10") (pintype "bidirectional"))
    )
    (net (code "11") (name "AREF_+10") (class "Default")
      (node (ref "C56") (pin "1") (pinfunction "1_1") (pintype "passive"))
      (node (ref "IC12") (pin "1") (pinfunction "C_1") (pintype "passive"))
      (node (ref "R57") (pin "2") (pinfunction "2_2") (pintype "passive"))
      (node (ref "R58") (pin "2") (pinfunction "2_2") (pintype "passive"))
      (node (ref "R59") (pin "2") (pinfunction "2_2") (pintype "passive"))
      (node (ref "R60") (pin "2") (pinfunction "2_2") (pintype "passive"))
      (node (ref "R63") (pin "2") (pinfunction "2_2") (pintype "passive"))
    )
    (net (code "12") (name "AREF_-10") (class "Default")
      (node (ref "C47") (pin "1") (pinfunction "1_1") (pintype "passive"))
      (node (ref "IC11") (pin "2") (pinfunction "A_2") (pintype "passive"))
      (node (ref "R10") (pin "1") (pinfunction "1_1") (pintype "passive"))
      (node (ref "R24") (pin "1") (pinfunction "1_1") (pintype "passive"))
      (node (ref "R26") (pin "1") (pinfunction "1_1") (pintype "passive"))
      (node (ref "R37") (pin "1") (pinfunction "1_1") (pintype "passive"))
      (node (ref "R44") (pin "1") (pinfunction "1_1") (pintype "passive"))
      (node (ref "R46") (pin "2") (pinfunction "2_2") (pintype "passive"))
      (node (ref "R64") (pin "1") (pinfunction "1_1") (pintype "passive"))
      (node (ref "R65") (pin "1") (pinfunction "1_1") (pintype "passive"))
      (node (ref "R9") (pin "1") (pinfunction "1_1") (pintype "passive"))
    )
    (net (code "13") (name "AREF_2.5") (class "Default")
      (node (ref "C17") (pin "1") (pinfunction "1_1") (pintype "passive"))
      (node (ref "IC1") (pin "2") (pinfunction "VREF_2") (pintype "power_in"))
      (node (ref "IC3") (pin "1") (pinfunction "C_1") (pintype "passive"))
      (node (ref "R8") (pin "2") (pinfunction "2_2") (pintype "passive"))
    )
    (net (code "14") (name "BARGRAPH_CS") (class "Default")
      (node (ref "JP3") (pin "5") (pinfunction "5_5") (pintype "passive"))
      (node (ref "UC1") (pin "43") (pinfunction "PB7/I2C1_SDA/TIM4_CH2_43") (pintype "bidirectional"))
    )
    (net (code "15") (name "BARGRAPH_MOSI") (class "Default")
      (node (ref "JP3") (pin "1") (pinfunction "1_1") (pintype "passive"))
      (node (ref "UC1") (pin "21") (pinfunction "PB10/I2C2_SCL/USART3_TX_21") (pintype "input"))
    )
    (net (code "16") (name "BARGRAPH_SCK") (class "Default")
      (node (ref "JP3") (pin "3") (pinfunction "3_3") (pintype "passive"))
      (node (ref "UC1") (pin "22") (pinfunction "PB11/I2C2_SDA/USART3_RX_22") (pintype "input"))
    )
    (net (code "17") (name "DAC_1") (class "Default")
      (node (ref "C22") (pin "1") (pinfunction "1_1") (pintype "passive"))
      (node (ref "R20") (pin "2") (pinfunction "2_2") (pintype "passive"))
      (node (ref "R30") (pin "1") (pinfunction "1_1") (pintype "passive"))
    )
    (net (code "18") (name "DAC_2") (class "Default")
      (node (ref "C23") (pin "1") (pinfunction "1_1") (pintype "passive"))
      (node (ref "R21") (pin "2") (pinfunction "2_2") (pintype "passive"))
      (node (ref "R29") (pin "1") (pinfunction "1_1") (pintype "passive"))
    )
    (net (code "19") (name "DAC_MOSI") (class "Default")
      (node (ref "IC1") (pin "7") (pinfunction "DIN_7") (pintype "bidirectional"))
      (node (ref "UC1") (pin "28") (pinfunction "PB15/SPI2_MOSI/TIM1_CH3N_28") (pintype "input"))
    )
    (net (code "20") (name "DAC_SCK") (class "Default")
      (node (ref "IC1") (pin "6") (pinfunction "SCLK_6") (pintype "bidirectional"))
      (node (ref "UC1") (pin "26") (pinfunction "PB13/SPI2_SCK/USART3_CTS/TIM1_CH1N_26") (pintype "input"))
    )
    (net (code "21") (name "DAC_SS") (class "Default")
      (node (ref "IC1") (pin "5") (pinfunction "~{SYNC}_5") (pintype "bidirectional"))
      (node (ref "UC1") (pin "25") (pinfunction "PB12/SPI2_NSS/I2C2_SMBA/USART3_CK/TIM1_BKIN_25") (pintype "input"))
    )
    (net (code "22") (name "GND") (class "Default")
      (node (ref "C1") (pin "2") (pinfunction "2_2") (pintype "passive"))
      (node (ref "C10") (pin "2") (pinfunction "2_2") (pintype "passive"))
      (node (ref "C11") (pin "-") (pinfunction "-_-") (pintype "passive"))
      (node (ref "C12") (pin "1") (pinfunction "1_1") (pintype "passive"))
      (node (ref "C13") (pin "2") (pinfunction "2_2") (pintype "passive"))
      (node (ref "C14") (pin "2") (pinfunction "2_2") (pintype "passive"))
      (node (ref "C15") (pin "2") (pinfunction "2_2") (pintype "passive"))
      (node (ref "C16") (pin "-") (pinfunction "-_-") (pintype "passive"))
      (node (ref "C17") (pin "2") (pinfunction "2_2") (pintype "passive"))
      (node (ref "C2") (pin "-") (pinfunction "-_-") (pintype "passive"))
      (node (ref "C20") (pin "2") (pinfunction "2_2") (pintype "passive"))
      (node (ref "C21") (pin "2") (pinfunction "2_2") (pintype "passive"))
      (node (ref "C22") (pin "2") (pinfunction "2_2") (pintype "passive"))
      (node (ref "C23") (pin "2") (pinfunction "2_2") (pintype "passive"))
      (node (ref "C24") (pin "-") (pinfunction "-_-") (pintype "passive"))
      (node (ref "C25") (pin "2") (pinfunction "2_2") (pintype "passive"))
      (node (ref "C28") (pin "+") (pinfunction "+_+") (pintype "passive"))
      (node (ref "C29") (pin "2") (pinfunction "2_2") (pintype "passive"))
      (node (ref "C3") (pin "2") (pinfunction "2_2") (pintype "passive"))
      (node (ref "C32") (pin "2") (pinfunction "2_2") (pintype "passive"))
      (node (ref "C33") (pin "1") (pinfunction "1_1") (pintype "passive"))
      (node (ref "C34") (pin "1") (pinfunction "1_1") (pintype "passive"))
      (node (ref "C35") (pin "2") (pinfunction "2_2") (pintype "passive"))
      (node (ref "C36") (pin "2") (pinfunction "2_2") (pintype "passive"))
      (node (ref "C37") (pin "2") (pinfunction "2_2") (pintype "passive"))
      (node (ref "C38") (pin "2") (pinfunction "2_2") (pintype "passive"))
      (node (ref "C39") (pin "1") (pinfunction "1_1") (pintype "passive"))
      (node (ref "C4") (pin "2") (pinfunction "2_2") (pintype "passive"))
      (node (ref "C41") (pin "2") (pinfunction "2_2") (pintype "passive"))
      (node (ref "C42") (pin "2") (pinfunction "2_2") (pintype "passive"))
      (node (ref "C44") (pin "1") (pinfunction "1_1") (pintype "passive"))
      (node (ref "C45") (pin "2") (pinfunction "2_2") (pintype "passive"))
      (node (ref "C46") (pin "2") (pinfunction "2_2") (pintype "passive"))
      (node (ref "C47") (pin "2") (pinfunction "2_2") (pintype "passive"))
      (node (ref "C48") (pin "1") (pinfunction "1_1") (pintype "passive"))
      (node (ref "C49") (pin "1") (pinfunction "1_1") (pintype "passive"))
      (node (ref "C5") (pin "1") (pinfunction "1_1") (pintype "passive"))
      (node (ref "C50") (pin "2") (pinfunction "2_2") (pintype "passive"))
      (node (ref "C51") (pin "2") (pinfunction "2_2") (pintype "passive"))
      (node (ref "C54") (pin "2") (pinfunction "2_2") (pintype "passive"))
      (node (ref "C55") (pin "2") (pinfunction "2_2") (pintype "passive"))
      (node (ref "C56") (pin "2") (pinfunction "2_2") (pintype "passive"))
      (node (ref "C6") (pin "2") (pinfunction "2_2") (pintype "passive"))
      (node (ref "C7") (pin "2") (pinfunction "2_2") (pintype "passive"))
      (node (ref "C8") (pin "2") (pinfunction "2_2") (pintype "passive"))
      (node (ref "C9") (pin "2") (pinfunction "2_2") (pintype "passive"))
      (node (ref "D1") (pin "1") (pinfunction "A_1") (pintype "passive"))
      (node (ref "D2") (pin "1") (pinfunction "A_1") (pintype "passive"))
      (node (ref "D4") (pin "A") (pinfunction "A_A") (pintype "passive"))
      (node (ref "D5") (pin "A") (pinfunction "A_A") (pintype "passive"))
      (node (ref "D6") (pin "C") (pinfunction "C_C") (pintype "passive"))
      (node (ref "IC1") (pin "8") (pinfunction "GND_8") (pintype "power_in"))
      (node (ref "IC10") (pin "3") (pinfunction "+IN_3") (pintype "input"))
      (node (ref "IC10") (pin "5") (pinfunction "+IN_5") (pintype "input"))
      (node (ref "IC11") (pin "1") (pinfunction "C_1") (pintype "passive"))
      (node (ref "IC12") (pin "2") (pinfunction "A_2") (pintype "passive"))
      (node (ref "IC2") (pin "1") (pinfunction "GND_1") (pintype "power_in"))
      (node (ref "IC3") (pin "2") (pinfunction "A_2") (pintype "passive"))
      (node (ref "IC4") (pin "10") (pinfunction "+IN_10") (pintype "input"))
      (node (ref "IC4") (pin "11") (pinfunction "V-_11") (pintype "power_in"))
      (node (ref "IC4") (pin "12") (pinfunction "+IN_12") (pintype "input"))
      (node (ref "IC4") (pin "3") (pinfunction "+IN_3") (pintype "input"))
      (node (ref "IC4") (pin "5") (pinfunction "+IN_5") (pintype "input"))
      (node (ref "IC5") (pin "3") (pinfunction "+IN_3") (pintype "input"))
      (node (ref "IC5") (pin "5") (pinfunction "+IN_5") (pintype "input"))
      (node (ref "IC6") (pin "3") (pinfunction "+IN_3") (pintype "input"))
      (node (ref "IC6") (pin "5") (pinfunction "+IN_5") (pintype "input"))
      (node (ref "IC7") (pin "3") (pinfunction "+IN_3") (pintype "input"))
      (node (ref "IC7") (pin "5") (pinfunction "+IN_5") (pintype "input"))
      (node (ref "IC8") (pin "8") (pinfunction "GND_8") (pintype "power_in"))
      (node (ref "IC9") (pin "8") (pinfunction "GND_8") (pintype "power_in"))
      (node (ref "J1") (pin "GND") (pinfunction "1_GND") (pintype "passive"))
      (node (ref "J1") (pin "GND2") (pinfunction "4_GND2") (pintype "passive"))
      (node (ref "J2") (pin "GND") (pinfunction "1_GND") (pintype "passive"))
      (node (ref "J2") (pin "GND2") (pinfunction "4_GND2") (pintype "passive"))
      (node (ref "J3") (pin "GND") (pinfunction "1_GND") (pintype "passive"))
      (node (ref "J3") (pin "GND2") (pinfunction "4_GND2") (pintype "passive"))
      (node (ref "J4") (pin "GND") (pinfunction "1_GND") (pintype "passive"))
      (node (ref "J4") (pin "GND2") (pinfunction "4_GND2") (pintype "passive"))
      (node (ref "J5") (pin "GND") (pinfunction "1_GND") (pintype "passive"))
      (node (ref "J5") (pin "GND2") (pinfunction "4_GND2") (pintype "passive"))
      (node (ref "J6") (pin "GND") (pinfunction "1_GND") (pintype "passive"))
      (node (ref "J6") (pin "GND2") (pinfunction "4_GND2") (pintype "passive"))
      (node (ref "J7") (pin "GND") (pinfunction "1_GND") (pintype "passive"))
      (node (ref "J7") (pin "GND2") (pinfunction "4_GND2") (pintype "passive"))
      (node (ref "J8") (pin "GND") (pinfunction "1_GND") (pintype "passive"))
      (node (ref "J8") (pin "GND2") (pinfunction "4_GND2") (pintype "passive"))
      (node (ref "JP3") (pin "2") (pinfunction "2_2") (pintype "passive"))
      (node (ref "JP6") (pin "3") (pinfunction "3_3") (pintype "passive"))
      (node (ref "JP6") (pin "4") (pinfunction "4_4") (pintype "passive"))
      (node (ref "JP6") (pin "5") (pinfunction "5_5") (pintype "passive"))
      (node (ref "JP6") (pin "6") (pinfunction "6_6") (pintype "passive"))
      (node (ref "JP6") (pin "7") (pinfunction "7_7") (pintype "passive"))
      (node (ref "JP6") (pin "8") (pinfunction "8_8") (pintype "passive"))
      (node (ref "JP7") (pin "3") (pinfunction "3_3") (pintype "passive"))
      (node (ref "JP7") (pin "5") (pinfunction "5_5") (pintype "passive"))
      (node (ref "JP7") (pin "9") (pinfunction "9_9") (pintype "passive"))
      (node (ref "R14") (pin "P$3") (pinfunction "A_P$3") (pintype "passive"))
      (node (ref "R15") (pin "P$3") (pinfunction "A_P$3") (pintype "passive"))
      (node (ref "R2") (pin "P$3") (pinfunction "A_P$3") (pintype "passive"))
      (node (ref "R3") (pin "P$3") (pinfunction "A_P$3") (pintype "passive"))
      (node (ref "R31") (pin "1") (pinfunction "1_1") (pintype "passive"))
      (node (ref "R32") (pin "P$3") (pinfunction "A_P$3") (pintype "passive"))
      (node (ref "R33") (pin "P$3") (pinfunction "A_P$3") (pintype "passive"))
      (node (ref "R45") (pin "1") (pinfunction "1_1") (pintype "passive"))
      (node (ref "SW1") (pin "1") (pinfunction "1_1") (pintype "passive"))
      (node (ref "SW1") (pin "2") (pinfunction "2_2") (pintype "passive"))
      (node (ref "SW2") (pin "1") (pinfunction "1_1") (pintype "passive"))
      (node (ref "SW2") (pin "2") (pinfunction "2_2") (pintype "passive"))
      (node (ref "SW3") (pin "1") (pinfunction "1_1") (pintype "passive"))
      (node (ref "SW3") (pin "2") (pinfunction "2_2") (pintype "passive"))
      (node (ref "UC1") (pin "20") (pinfunction "PB2/BOOT1_20") (pintype "bidirectional"))
      (node (ref "UC1") (pin "23") (pinfunction "VSS_1_23") (pintype "power_in"))
      (node (ref "UC1") (pin "35") (pinfunction "VSS_2_35") (pintype "power_in"))
      (node (ref "UC1") (pin "44") (pinfunction "BOOT0_44") (pintype "input"))
      (node (ref "UC1") (pin "47") (pinfunction "VSS_3_47") (pintype "power_in"))
      (node (ref "UC1") (pin "8") (pinfunction "VSS_A_8") (pintype "power_in"))
    )
    (net (code "23") (name "JTCK") (class "Default")
      (node (ref "JP7") (pin "4") (pinfunction "4_4") (pintype "passive"))
      (node (ref "UC1") (pin "37") (pinfunction "PA14/JTCK/SWCLK_37") (pintype "bidirectional"))
    )
    (net (code "24") (name "JTDI") (class "Default")
      (node (ref "JP7") (pin "8") (pinfunction "8_8") (pintype "passive"))
      (node (ref "UC1") (pin "38") (pinfunction "PA15/JTDI_38") (pintype "bidirectional"))
    )
    (net (code "25") (name "JTDO") (class "Default")
      (node (ref "JP7") (pin "6") (pinfunction "6_6") (pintype "passive"))
      (node (ref "UC1") (pin "39") (pinfunction "PB3/JTDO_39") (pintype "bidirectional"))
    )
    (net (code "26") (name "JTMS") (class "Default")
      (node (ref "JP7") (pin "2") (pinfunction "2_2") (pintype "passive"))
      (node (ref "UC1") (pin "34") (pinfunction "PA13/JTMS/SWDIO_34") (pintype "bidirectional"))
    )
    (net (code "27") (name "Net-(C20-Pad1)") (class "Default")
      (node (ref "C20") (pin "1") (pinfunction "1_1") (pintype "passive"))
      (node (ref "R16") (pin "2") (pinfunction "2_2") (pintype "passive"))
      (node (ref "R20") (pin "1") (pinfunction "1_1") (pintype "passive"))
    )
    (net (code "28") (name "Net-(C21-Pad1)") (class "Default")
      (node (ref "C21") (pin "1") (pinfunction "1_1") (pintype "passive"))
      (node (ref "R17") (pin "2") (pinfunction "2_2") (pintype "passive"))
      (node (ref "R21") (pin "1") (pinfunction "1_1") (pintype "passive"))
    )
    (net (code "29") (name "Net-(C36-Pad1)") (class "Default")
      (node (ref "C36") (pin "1") (pinfunction "1_1") (pintype "passive"))
      (node (ref "R41") (pin "1") (pinfunction "1_1") (pintype "passive"))
    )
    (net (code "30") (name "Net-(C37-Pad1)") (class "Default")
      (node (ref "C37") (pin "1") (pinfunction "1_1") (pintype "passive"))
      (node (ref "R40") (pin "1") (pinfunction "1_1") (pintype "passive"))
    )
    (net (code "31") (name "Net-(C38-Pad1)") (class "Default")
      (node (ref "C38") (pin "1") (pinfunction "1_1") (pintype "passive"))
      (node (ref "R38") (pin "1") (pinfunction "1_1") (pintype "passive"))
    )
    (net (code "32") (name "Net-(C42-Pad1)") (class "Default")
      (node (ref "C42") (pin "1") (pinfunction "1_1") (pintype "passive"))
      (node (ref "R43") (pin "1") (pinfunction "1_1") (pintype "passive"))
    )
    (net (code "33") (name "Net-(C50-Pad1)") (class "Default")
      (node (ref "C50") (pin "1") (pinfunction "1_1") (pintype "passive"))
      (node (ref "R47") (pin "1") (pinfunction "1_1") (pintype "passive"))
    )
    (net (code "34") (name "Net-(C51-Pad1)") (class "Default")
      (node (ref "C51") (pin "1") (pinfunction "1_1") (pintype "passive"))
      (node (ref "R48") (pin "1") (pinfunction "1_1") (pintype "passive"))
    )
    (net (code "35") (name "Net-(C54-Pad1)") (class "Default")
      (node (ref "C54") (pin "1") (pinfunction "1_1") (pintype "passive"))
      (node (ref "R50") (pin "1") (pinfunction "1_1") (pintype "passive"))
    )
    (net (code "36") (name "Net-(C55-Pad1)") (class "Default")
      (node (ref "C55") (pin "1") (pinfunction "1_1") (pintype "passive"))
      (node (ref "R55") (pin "1") (pinfunction "1_1") (pintype "passive"))
    )
    (net (code "37") (name "Net-(D3-PadA)") (class "Default")
      (node (ref "D3") (pin "A") (pinfunction "A_A") (pintype "passive"))
      (node (ref "JP6") (pin "1") (pinfunction "1_1") (pintype "passive"))
      (node (ref "JP6") (pin "2") (pinfunction "2_2") (pintype "passive"))
    )
    (net (code "38") (name "Net-(IC1-OUTA)") (class "Default")
      (node (ref "IC1") (pin "4") (pinfunction "OUTA_4") (pintype "output"))
      (node (ref "R17") (pin "1") (pinfunction "1_1") (pintype "passive"))
    )
    (net (code "39") (name "Net-(IC1-OUTB)") (class "Default")
      (node (ref "IC1") (pin "3") (pinfunction "OUTB_3") (pintype "input"))
      (node (ref "R16") (pin "1") (pinfunction "1_1") (pintype "passive"))
    )
    (net (code "40") (name "Net-(IC2-VIN)") (class "Default")
      (node (ref "C16") (pin "+") (pinfunction "+_+") (pintype "passive"))
      (node (ref "IC2") (pin "3") (pinfunction "VIN_3") (pintype "input"))
      (node (ref "R11") (pin "2") (pinfunction "2_2") (pintype "passive"))
    )
    (net (code "41") (name "Net-(IC4A--IN)") (class "Default")
      (node (ref "C26") (pin "1") (pinfunction "1_1") (pintype "passive"))
      (node (ref "IC4") (pin "2") (pinfunction "-IN_2") (pintype "input"))
      (node (ref "R22") (pin "1") (pinfunction "1_1") (pintype "passive"))
      (node (ref "R25") (pin "2") (pinfunction "2_2") (pintype "passive"))
      (node (ref "R26") (pin "2") (pinfunction "2_2") (pintype "passive"))
    )
    (net (code "42") (name "Net-(IC4B--IN)") (class "Default")
      (node (ref "C27") (pin "1") (pinfunction "1_1") (pintype "passive"))
      (node (ref "IC4") (pin "6") (pinfunction "-IN_6") (pintype "input"))
      (node (ref "R23") (pin "1") (pinfunction "1_1") (pintype "passive"))
      (node (ref "R24") (pin "2") (pinfunction "2_2") (pintype "passive"))
      (node (ref "R28") (pin "2") (pinfunction "2_2") (pintype "passive"))
    )
    (net (code "43") (name "Net-(IC4C--IN)") (class "Default")
      (node (ref "C19") (pin "1") (pinfunction "1_1") (pintype "passive"))
      (node (ref "IC4") (pin "9") (pinfunction "-IN_9") (pintype "input"))
      (node (ref "R10") (pin "2") (pinfunction "2_2") (pintype "passive"))
      (node (ref "R13") (pin "2") (pinfunction "2_2") (pintype "passive"))
      (node (ref "R19") (pin "1") (pinfunction "1_1") (pintype "passive"))
    )
    (net (code "44") (name "Net-(IC4D--IN)") (class "Default")
      (node (ref "C18") (pin "1") (pinfunction "1_1") (pintype "passive"))
      (node (ref "IC4") (pin "13") (pinfunction "-IN_13") (pintype "input"))
      (node (ref "R12") (pin "2") (pinfunction "2_2") (pintype "passive"))
      (node (ref "R18") (pin "1") (pinfunction "1_1") (pintype "passive"))
      (node (ref "R9") (pin "2") (pinfunction "2_2") (pintype "passive"))
    )
    (net (code "45") (name "Net-(IC5A--IN)") (class "Default")
      (node (ref "IC5") (pin "1") (pinfunction "OUT_1") (pintype "output"))
      (node (ref "IC5") (pin "2") (pinfunction "-IN_2") (pintype "input"))
    )
    (net (code "46") (name "Net-(IC5B--IN)") (class "Default")
      (node (ref "C30") (pin "1") (pinfunction "1_1") (pintype "passive"))
      (node (ref "IC5") (pin "6") (pinfunction "-IN_6") (pintype "input"))
      (node (ref "IC8") (pin "12") (pinfunction "OUT_12") (pintype "output"))
      (node (ref "R30") (pin "2") (pinfunction "2_2") (pintype "passive"))
      (node (ref "R32") (pin "P$1") (pinfunction "E_P$1") (pintype "passive"))
      (node (ref "R65") (pin "2") (pinfunction "2_2") (pintype "passive"))
    )
    (net (code "47") (name "Net-(IC6A--IN)") (class "Default")
      (node (ref "IC6") (pin "1") (pinfunction "OUT_1") (pintype "output"))
      (node (ref "IC6") (pin "2") (pinfunction "-IN_2") (pintype "input"))
    )
    (net (code "48") (name "Net-(IC6B--IN)") (class "Default")
      (node (ref "C31") (pin "1") (pinfunction "1_1") (pintype "passive"))
      (node (ref "IC6") (pin "6") (pinfunction "-IN_6") (pintype "input"))
      (node (ref "IC9") (pin "13") (pinfunction "OUT_13") (pintype "output"))
      (node (ref "R29") (pin "2") (pinfunction "2_2") (pintype "passive"))
      (node (ref "R33") (pin "P$1") (pinfunction "E_P$1") (pintype "passive"))
      (node (ref "R64") (pin "2") (pinfunction "2_2") (pintype "passive"))
    )
    (net (code "49") (name "Net-(IC7A--IN)") (class "Default")
      (node (ref "C53") (pin "1") (pinfunction "1_1") (pintype "passive"))
      (node (ref "IC7") (pin "2") (pinfunction "-IN_2") (pintype "input"))
      (node (ref "IC8") (pin "4") (pinfunction "OUT_4") (pintype "output"))
    )
    (net (code "50") (name "Net-(IC7A-OUT)") (class "Default")
      (node (ref "C53") (pin "2") (pinfunction "2_2") (pintype "passive"))
      (node (ref "IC7") (pin "1") (pinfunction "OUT_1") (pintype "output"))
      (node (ref "R49") (pin "2") (pinfunction "2_2") (pintype "passive"))
      (node (ref "R51") (pin "1") (pinfunction "1_1") (pintype "passive"))
    )
    (net (code "51") (name "Net-(IC7B--IN)") (class "Default")
      (node (ref "C40") (pin "1") (pinfunction "1_1") (pintype "passive"))
      (node (ref "IC7") (pin "6") (pinfunction "-IN_6") (pintype "input"))
      (node (ref "IC8") (pin "5") (pinfunction "OUT_5") (pintype "output"))
    )
    (net (code "52") (name "Net-(IC7B-OUT)") (class "Default")
      (node (ref "C40") (pin "2") (pinfunction "2_2") (pintype "passive"))
      (node (ref "IC7") (pin "7") (pinfunction "OUT_7") (pintype "output"))
      (node (ref "R52") (pin "2") (pinfunction "2_2") (pintype "passive"))
      (node (ref "R61") (pin "1") (pinfunction "1_1") (pintype "passive"))
    )
    (net (code "53") (name "Net-(IC8A-IN)") (class "Default")
      (node (ref "IC8") (pin "13") (pinfunction "OUT_13") (pintype "output"))
      (node (ref "IC8") (pin "2") (pinfunction "IN_2") (pintype "input"))
      (node (ref "R49") (pin "1") (pinfunction "1_1") (pintype "passive"))
      (node (ref "R50") (pin "2") (pinfunction "2_2") (pintype "passive"))
    )
    (net (code "54") (name "Net-(IC8B-IN)") (class "Default")
      (node (ref "IC8") (pin "7") (pinfunction "IN_7") (pintype "input"))
      (node (ref "R47") (pin "2") (pinfunction "2_2") (pintype "passive"))
      (node (ref "R51") (pin "2") (pinfunction "2_2") (pintype "passive"))
      (node (ref "R52") (pin "1") (pinfunction "1_1") (pintype "passive"))
    )
    (net (code "55") (name "Net-(IC8C-CTRL)") (class "Default")
      (node (ref "IC8") (pin "11") (pinfunction "CTRL_11") (pintype "input"))
      (node (ref "R27") (pin "P$2") (pinfunction "S_P$2") (pintype "passive"))
    )
    (net (code "56") (name "Net-(IC8C-IN)") (class "Default")
      (node (ref "IC8") (pin "10") (pinfunction "IN_10") (pintype "input"))
      (node (ref "R37") (pin "2") (pinfunction "2_2") (pintype "passive"))
      (node (ref "R38") (pin "2") (pinfunction "2_2") (pintype "passive"))
    )
    (net (code "57") (name "Net-(IC8D-IN)") (class "Default")
      (node (ref "IC8") (pin "15") (pinfunction "IN_15") (pintype "input"))
      (node (ref "R41") (pin "2") (pinfunction "2_2") (pintype "passive"))
      (node (ref "R42") (pin "2") (pinfunction "2_2") (pintype "passive"))
    )
    (net (code "58") (name "Net-(IC9A-IN)") (class "Default")
      (node (ref "IC9") (pin "2") (pinfunction "IN_2") (pintype "input"))
      (node (ref "R48") (pin "2") (pinfunction "2_2") (pintype "passive"))
      (node (ref "R53") (pin "1") (pinfunction "1_1") (pintype "passive"))
      (node (ref "R54") (pin "2") (pinfunction "2_2") (pintype "passive"))
    )
    (net (code "59") (name "Net-(IC9B-IN)") (class "Default")
      (node (ref "IC9") (pin "12") (pinfunction "OUT_12") (pintype "output"))
      (node (ref "IC9") (pin "7") (pinfunction "IN_7") (pintype "input"))
      (node (ref "R55") (pin "2") (pinfunction "2_2") (pintype "passive"))
      (node (ref "R56") (pin "1") (pinfunction "1_1") (pintype "passive"))
    )
    (net (code "60") (name "Net-(IC9C-IN)") (class "Default")
      (node (ref "IC9") (pin "10") (pinfunction "IN_10") (pintype "input"))
      (node (ref "R39") (pin "2") (pinfunction "2_2") (pintype "passive"))
      (node (ref "R40") (pin "2") (pinfunction "2_2") (pintype "passive"))
    )
    (net (code "61") (name "Net-(IC9D-CTRL)") (class "Default")
      (node (ref "IC9") (pin "14") (pinfunction "CTRL_14") (pintype "input"))
      (node (ref "R36") (pin "P$2") (pinfunction "S_P$2") (pintype "passive"))
    )
    (net (code "62") (name "Net-(IC9D-IN)") (class "Default")
      (node (ref "IC9") (pin "15") (pinfunction "IN_15") (pintype "input"))
      (node (ref "R43") (pin "2") (pinfunction "2_2") (pintype "passive"))
      (node (ref "R44") (pin "2") (pinfunction "2_2") (pintype "passive"))
    )
    (net (code "63") (name "Net-(IC10A--IN)") (class "Default")
      (node (ref "C52") (pin "1") (pinfunction "1_1") (pintype "passive"))
      (node (ref "IC10") (pin "2") (pinfunction "-IN_2") (pintype "input"))
      (node (ref "IC9") (pin "5") (pinfunction "OUT_5") (pintype "output"))
    )
    (net (code "64") (name "Net-(IC10A-OUT)") (class "Default")
      (node (ref "C52") (pin "2") (pinfunction "2_2") (pintype "passive"))
      (node (ref "IC10") (pin "1") (pinfunction "OUT_1") (pintype "output"))
      (node (ref "R54") (pin "1") (pinfunction "1_1") (pintype "passive"))
      (node (ref "R56") (pin "2") (pinfunction "2_2") (pintype "passive"))
    )
    (net (code "65") (name "Net-(IC10B--IN)") (class "Default")
      (node (ref "C43") (pin "1") (pinfunction "1_1") (pintype "passive"))
      (node (ref "IC10") (pin "6") (pinfunction "-IN_6") (pintype "input"))
      (node (ref "IC9") (pin "4") (pinfunction "OUT_4") (pintype "output"))
    )
    (net (code "66") (name "Net-(IC10B-OUT)") (class "Default")
      (node (ref "C43") (pin "2") (pinfunction "2_2") (pintype "passive"))
      (node (ref "IC10") (pin "7") (pinfunction "OUT_7") (pintype "output"))
      (node (ref "R53") (pin "2") (pinfunction "2_2") (pintype "passive"))
      (node (ref "R62") (pin "1") (pinfunction "1_1") (pintype "passive"))
    )
    (net (code "67") (name "Net-(J1-2)") (class "Default")
      (node (ref "J1") (pin "TIP") (pinfunction "2_TIP") (pintype "passive"))
      (node (ref "R25") (pin "1") (pinfunction "1_1") (pintype "passive"))
    )
    (net (code "68") (name "Net-(J2-2)") (class "Default")
      (node (ref "J2") (pin "TIP") (pinfunction "2_TIP") (pintype "passive"))
      (node (ref "R12") (pin "1") (pinfunction "1_1") (pintype "passive"))
      (node (ref "R42") (pin "1") (pinfunction "1_1") (pintype "passive"))
    )
    (net (code "69") (name "Net-(J2-3)") (class "Default")
      (node (ref "J2") (pin "SW") (pinfunction "3_SW") (pintype "passive"))
      (node (ref "R59") (pin "1") (pinfunction "1_1") (pintype "passive"))
    )
    (net (code "70") (name "Net-(J3-2)") (class "Default")
      (node (ref "J3") (pin "TIP") (pinfunction "2_TIP") (pintype "passive"))
      (node (ref "R13") (pin "1") (pinfunction "1_1") (pintype "passive"))
      (node (ref "R39") (pin "1") (pinfunction "1_1") (pintype "passive"))
    )
    (net (code "71") (name "Net-(J3-3)") (class "Default")
      (node (ref "J3") (pin "SW") (pinfunction "3_SW") (pintype "passive"))
      (node (ref "R58") (pin "1") (pinfunction "1_1") (pintype "passive"))
    )
    (net (code "72") (name "Net-(J4-2)") (class "Default")
      (node (ref "J4") (pin "TIP") (pinfunction "2_TIP") (pintype "passive"))
      (node (ref "R28") (pin "1") (pinfunction "1_1") (pintype "passive"))
    )
    (net (code "73") (name "Net-(J5-2)") (class "Default")
      (node (ref "J5") (pin "TIP") (pinfunction "2_TIP") (pintype "passive"))
      (node (ref "R34") (pin "1") (pinfunction "1_1") (pintype "passive"))
    )
    (net (code "74") (name "Net-(J5-3)") (class "Default")
      (node (ref "J5") (pin "SW") (pinfunction "3_SW") (pintype "passive"))
      (node (ref "R60") (pin "1") (pinfunction "1_1") (pintype "passive"))
    )
    (net (code "75") (name "Net-(J6-2)") (class "Default")
      (node (ref "J6") (pin "TIP") (pinfunction "2_TIP") (pintype "passive"))
      (node (ref "R61") (pin "2") (pinfunction "2_2") (pintype "passive"))
    )
    (net (code "76") (name "Net-(J7-2)") (class "Default")
      (node (ref "J7") (pin "TIP") (pinfunction "2_TIP") (pintype "passive"))
      (node (ref "R62") (pin "2") (pinfunction "2_2") (pintype "passive"))
    )
    (net (code "77") (name "Net-(J8-2)") (class "Default")
      (node (ref "J8") (pin "TIP") (pinfunction "2_TIP") (pintype "passive"))
      (node (ref "R35") (pin "1") (pinfunction "1_1") (pintype "passive"))
    )
    (net (code "78") (name "Net-(J8-3)") (class "Default")
      (node (ref "J8") (pin "SW") (pinfunction "3_SW") (pintype "passive"))
      (node (ref "R63") (pin "1") (pinfunction "1_1") (pintype "passive"))
    )
    (net (code "79") (name "Net-(JP6-Pad10)") (class "Default")
      (node (ref "JP6") (pin "10") (pinfunction "10_10") (pintype "passive"))
      (node (ref "JP6") (pin "9") (pinfunction "9_9") (pintype "passive"))
      (node (ref "P1") (pin "2") (pinfunction "2_2") (pintype "bidirectional"))
    )
    (net (code "80") (name "Net-(R27-A)") (class "Default")
      (node (ref "R27") (pin "P$3") (pinfunction "A_P$3") (pintype "passive"))
      (node (ref "R31") (pin "2") (pinfunction "2_2") (pintype "passive"))
    )
    (net (code "81") (name "Net-(R32-S)") (class "Default")
      (node (ref "R32") (pin "P$2") (pinfunction "S_P$2") (pintype "passive"))
      (node (ref "R34") (pin "2") (pinfunction "2_2") (pintype "passive"))
    )
    (net (code "82") (name "Net-(R33-S)") (class "Default")
      (node (ref "R33") (pin "P$2") (pinfunction "S_P$2") (pintype "passive"))
      (node (ref "R35") (pin "2") (pinfunction "2_2") (pintype "passive"))
    )
    (net (code "83") (name "Net-(R36-A)") (class "Default")
      (node (ref "R36") (pin "P$3") (pinfunction "A_P$3") (pintype "passive"))
      (node (ref "R45") (pin "2") (pinfunction "2_2") (pintype "passive"))
    )
    (net (code "84") (name "Net-(UC1-PA10{slash}USART1_RX{slash}TIM1_CH3)") (class "Default")
      (node (ref "R4") (pin "1") (pinfunction "1_1") (pintype "passive"))
      (node (ref "UC1") (pin "31") (pinfunction "PA10/USART1_RX/TIM1_CH3_31") (pintype "bidirectional"))
    )
    (net (code "85") (name "Net-(UC1-PA11{slash}USART1_CTS{slash}CAN_RX{slash}TIM1_CH4{slash}USBDM)") (class "Default")
      (node (ref "R5") (pin "1") (pinfunction "1_1") (pintype "passive"))
      (node (ref "UC1") (pin "32") (pinfunction "PA11/USART1_CTS/CAN_RX/TIM1_CH4/USBDM_32") (pintype "bidirectional"))
    )
    (net (code "86") (name "Net-(UC1-PD0-OSC_IN)") (class "Default")
      (node (ref "C5") (pin "2") (pinfunction "2_2") (pintype "passive"))
      (node (ref "Q1") (pin "2") (pinfunction "2_2") (pintype "passive"))
      (node (ref "UC1") (pin "5") (pinfunction "PD0-OSC_IN_5") (pintype "input"))
    )
    (net (code "87") (name "Net-(UC1-PD1-OSC_OUT)") (class "Default")
      (node (ref "C12") (pin "2") (pinfunction "2_2") (pintype "passive"))
      (node (ref "Q1") (pin "1") (pinfunction "1_1") (pintype "passive"))
      (node (ref "UC1") (pin "6") (pinfunction "PD1-OSC_OUT_6") (pintype "input"))
    )
    (net (code "88") (name "PWM_CUTOFF_1") (class "Default")
      (node (ref "C6") (pin "1") (pinfunction "1_1") (pintype "passive"))
      (node (ref "IC8") (pin "3") (pinfunction "CTRL_3") (pintype "input"))
      (node (ref "IC8") (pin "6") (pinfunction "CTRL_6") (pintype "input"))
      (node (ref "R4") (pin "2") (pinfunction "2_2") (pintype "passive"))
    )
    (net (code "89") (name "PWM_CUTOFF_2") (class "Default")
      (node (ref "C7") (pin "1") (pinfunction "1_1") (pintype "passive"))
      (node (ref "IC9") (pin "3") (pinfunction "CTRL_3") (pintype "input"))
      (node (ref "IC9") (pin "6") (pinfunction "CTRL_6") (pintype "input"))
      (node (ref "R5") (pin "2") (pinfunction "2_2") (pintype "passive"))
    )
    (net (code "90") (name "RESET") (class "Default")
      (node (ref "JP7") (pin "10") (pinfunction "10_10") (pintype "passive"))
      (node (ref "R1") (pin "1") (pinfunction "1_1") (pintype "passive"))
      (node (ref "UC1") (pin "7") (pinfunction "NRST_7") (pintype "input"))
    )
    (net (code "91") (name "SHAPE_1") (class "Default")
      (node (ref "R2") (pin "P$2") (pinfunction "S_P$2") (pintype "passive"))
      (node (ref "UC1") (pin "12") (pinfunction "PA2/USART2_TX/ADC12_IN2/TIM2_CH3_12") (pintype "bidirectional"))
    )
    (net (code "92") (name "SHAPE_2") (class "Default")
      (node (ref "R3") (pin "P$2") (pinfunction "S_P$2") (pintype "passive"))
      (node (ref "UC1") (pin "11") (pinfunction "PA1/USART2_RTS/ADC12_IN1/TIM2_CH2_11") (pintype "bidirectional"))
    )
    (net (code "93") (name "SW_METER") (class "Default")
      (node (ref "SW3") (pin "3") (pinfunction "3_3") (pintype "passive"))
      (node (ref "SW3") (pin "4") (pinfunction "4_4") (pintype "passive"))
      (node (ref "UC1") (pin "42") (pinfunction "PB6/I2C1_SCL/TIM4_CH1_42") (pintype "input"))
    )
    (net (code "94") (name "SW_MODE_1") (class "Default")
      (node (ref "SW1") (pin "3") (pinfunction "3_3") (pintype "passive"))
      (node (ref "SW1") (pin "4") (pinfunction "4_4") (pintype "passive"))
      (node (ref "UC1") (pin "41") (pinfunction "PB5/I2C1_SMBA_41") (pintype "input"))
    )
    (net (code "95") (name "SW_MODE_2") (class "Default")
      (node (ref "SW2") (pin "3") (pinfunction "3_3") (pintype "passive"))
      (node (ref "SW2") (pin "4") (pinfunction "4_4") (pintype "passive"))
      (node (ref "UC1") (pin "40") (pinfunction "PB4/NJTRST_40") (pintype "bidirectional"))
    )
    (net (code "96") (name "VCA_CONTROL_1") (class "Default")
      (node (ref "C30") (pin "2") (pinfunction "2_2") (pintype "passive"))
      (node (ref "D5") (pin "C") (pinfunction "C_C") (pintype "passive"))
      (node (ref "IC5") (pin "7") (pinfunction "OUT_7") (pintype "output"))
      (node (ref "IC8") (pin "14") (pinfunction "CTRL_14") (pintype "input"))
      (node (ref "R27") (pin "P$1") (pinfunction "E_P$1") (pintype "passive"))
      (node (ref "R6") (pin "2") (pinfunction "2_2") (pintype "passive"))
      (node (ref "TP1") (pin "P$1") (pinfunction "1_P$1") (pintype "bidirectional"))
    )
    (net (code "97") (name "VCA_CONTROL_2") (class "Default")
      (node (ref "C31") (pin "2") (pinfunction "2_2") (pintype "passive"))
      (node (ref "D4") (pin "C") (pinfunction "C_C") (pintype "passive"))
      (node (ref "IC6") (pin "7") (pinfunction "OUT_7") (pintype "output"))
      (node (ref "IC9") (pin "11") (pinfunction "CTRL_11") (pintype "input"))
      (node (ref "R36") (pin "P$1") (pinfunction "E_P$1") (pintype "passive"))
      (node (ref "R7") (pin "2") (pinfunction "2_2") (pintype "passive"))
      (node (ref "TP2") (pin "P$1") (pinfunction "1_P$1") (pintype "bidirectional"))
    )
    (net (code "98") (name "VCC") (class "Default")
      (node (ref "C24") (pin "+") (pinfunction "+_+") (pintype "passive"))
      (node (ref "C29") (pin "1") (pinfunction "1_1") (pintype "passive"))
      (node (ref "C32") (pin "1") (pinfunction "1_1") (pintype "passive"))
      (node (ref "C35") (pin "1") (pinfunction "1_1") (pintype "passive"))
      (node (ref "C41") (pin "1") (pinfunction "1_1") (pintype "passive"))
      (node (ref "C45") (pin "1") (pinfunction "1_1") (pintype "passive"))
      (node (ref "C46") (pin "1") (pinfunction "1_1") (pintype "passive"))
      (node (ref "D3") (pin "C") (pinfunction "C_C") (pintype "passive"))
      (node (ref "IC10") (pin "8") (pinfunction "V+_8") (pintype "power_in"))
      (node (ref "IC5") (pin "8") (pinfunction "V+_8") (pintype "power_in"))
      (node (ref "IC6") (pin "8") (pinfunction "V+_8") (pintype "power_in"))
      (node (ref "IC7") (pin "8") (pinfunction "V+_8") (pintype "power_in"))
      (node (ref "IC8") (pin "16") (pinfunction "V+_16") (pintype "power_in"))
      (node (ref "IC9") (pin "16") (pinfunction "V+_16") (pintype "power_in"))
      (node (ref "R11") (pin "1") (pinfunction "1_1") (pintype "passive"))
      (node (ref "R57") (pin "1") (pinfunction "1_1") (pintype "passive"))
    )
    (net (code "99") (name "VEE") (class "Default")
      (node (ref "C28") (pin "-") (pinfunction "-_-") (pintype "passive"))
      (node (ref "C33") (pin "2") (pinfunction "2_2") (pintype "passive"))
      (node (ref "C34") (pin "2") (pinfunction "2_2") (pintype "passive"))
      (node (ref "C39") (pin "2") (pinfunction "2_2") (pintype "passive"))
      (node (ref "C44") (pin "2") (pinfunction "2_2") (pintype "passive"))
      (node (ref "C48") (pin "2") (pinfunction "2_2") (pintype "passive"))
      (node (ref "C49") (pin "2") (pinfunction "2_2") (pintype "passive"))
      (node (ref "D6") (pin "A") (pinfunction "A_A") (pintype "passive"))
      (node (ref "IC10") (pin "4") (pinfunction "V-_4") (pintype "power_in"))
      (node (ref "IC5") (pin "4") (pinfunction "V-_4") (pintype "power_in"))
      (node (ref "IC6") (pin "4") (pinfunction "V-_4") (pintype "power_in"))
      (node (ref "IC7") (pin "4") (pinfunction "V-_4") (pintype "power_in"))
      (node (ref "IC8") (pin "9") (pinfunction "V-_9") (pintype "power_in"))
      (node (ref "IC9") (pin "9") (pinfunction "V-_9") (pintype "power_in"))
      (node (ref "P1") (pin "1") (pinfunction "1_1") (pintype "bidirectional"))
      (node (ref "R46") (pin "1") (pinfunction "1_1") (pintype "passive"))
    )
    (net (code "100") (name "unconnected-(IC8E-MODE-Pad1)") (class "Default")
      (node (ref "IC8") (pin "1") (pinfunction "MODE_1") (pintype "input"))
    )
    (net (code "101") (name "unconnected-(IC9E-MODE-Pad1)") (class "Default")
      (node (ref "IC9") (pin "1") (pinfunction "MODE_1") (pintype "input"))
    )
    (net (code "102") (name "unconnected-(J1-3-PadSW)") (class "Default")
      (node (ref "J1") (pin "SW") (pinfunction "3_SW") (pintype "passive"))
    )
    (net (code "103") (name "unconnected-(J4-3-PadSW)") (class "Default")
      (node (ref "J4") (pin "SW") (pinfunction "3_SW") (pintype "passive"))
    )
    (net (code "104") (name "unconnected-(J6-3-PadSW)") (class "Default")
      (node (ref "J6") (pin "SW") (pinfunction "3_SW") (pintype "passive"))
    )
    (net (code "105") (name "unconnected-(J7-3-PadSW)") (class "Default")
      (node (ref "J7") (pin "SW") (pinfunction "3_SW") (pintype "passive"))
    )
    (net (code "106") (name "unconnected-(JP7-Pad7)") (class "Default")
      (node (ref "JP7") (pin "7") (pinfunction "7_7") (pintype "passive"))
    )
    (net (code "107") (name "unconnected-(UC1-PA8{slash}USART1_CK{slash}TIM1_CH1{slash}MCO-Pad29)") (class "Default")
      (node (ref "UC1") (pin "29") (pinfunction "PA8/USART1_CK/TIM1_CH1/MCO_29") (pintype "bidirectional"))
    )
    (net (code "108") (name "unconnected-(UC1-PA9{slash}USART1_TX{slash}TIM1_CH2-Pad30)") (class "Default")
      (node (ref "UC1") (pin "30") (pinfunction "PA9/USART1_TX/TIM1_CH2_30") (pintype "input"))
    )
    (net (code "109") (name "unconnected-(UC1-PA12{slash}USART1_RTS{slash}CAN_TX{slash}TIM1_ETR{slash}USBDP-Pad33)") (class "Default")
      (node (ref "UC1") (pin "33") (pinfunction "PA12/USART1_RTS/CAN_TX/TIM1_ETR/USBDP_33") (pintype "bidirectional"))
    )
    (net (code "110") (name "unconnected-(UC1-PB8{slash}TIM4_CH3-Pad45)") (class "Default")
      (node (ref "UC1") (pin "45") (pinfunction "PB8/TIM4_CH3_45") (pintype "bidirectional"))
    )
    (net (code "111") (name "unconnected-(UC1-PB9{slash}TIM4_CH4-Pad46)") (class "Default")
      (node (ref "UC1") (pin "46") (pinfunction "PB9/TIM4_CH4_46") (pintype "input"))
    )
    (net (code "112") (name "unconnected-(UC1-PB14{slash}SPI2_MISO{slash}USART3_RTS{slash}TIM1_CH2N-Pad27)") (class "Default")
      (node (ref "UC1") (pin "27") (pinfunction "PB14/SPI2_MISO/USART3_RTS/TIM1_CH2N_27") (pintype "input"))
    )
    (net (code "113") (name "unconnected-(UC1-PC13-TAMPER-RTC-Pad2)") (class "Default")
      (node (ref "UC1") (pin "2") (pinfunction "PC13-TAMPER-RTC_2") (pintype "input"))
    )
    (net (code "114") (name "unconnected-(UC1-PC14-OSC32_IN-Pad3)") (class "Default")
      (node (ref "UC1") (pin "3") (pinfunction "PC14-OSC32_IN_3") (pintype "input"))
    )
    (net (code "115") (name "unconnected-(UC1-PC15-OSC32_OUT-Pad4)") (class "Default")
      (node (ref "UC1") (pin "4") (pinfunction "PC15-OSC32_OUT_4") (pintype "input"))
    )
  )
)
